# vme_can_fpga_bridge.net
KiCad netlist of a schematic drawn in Altium Designer
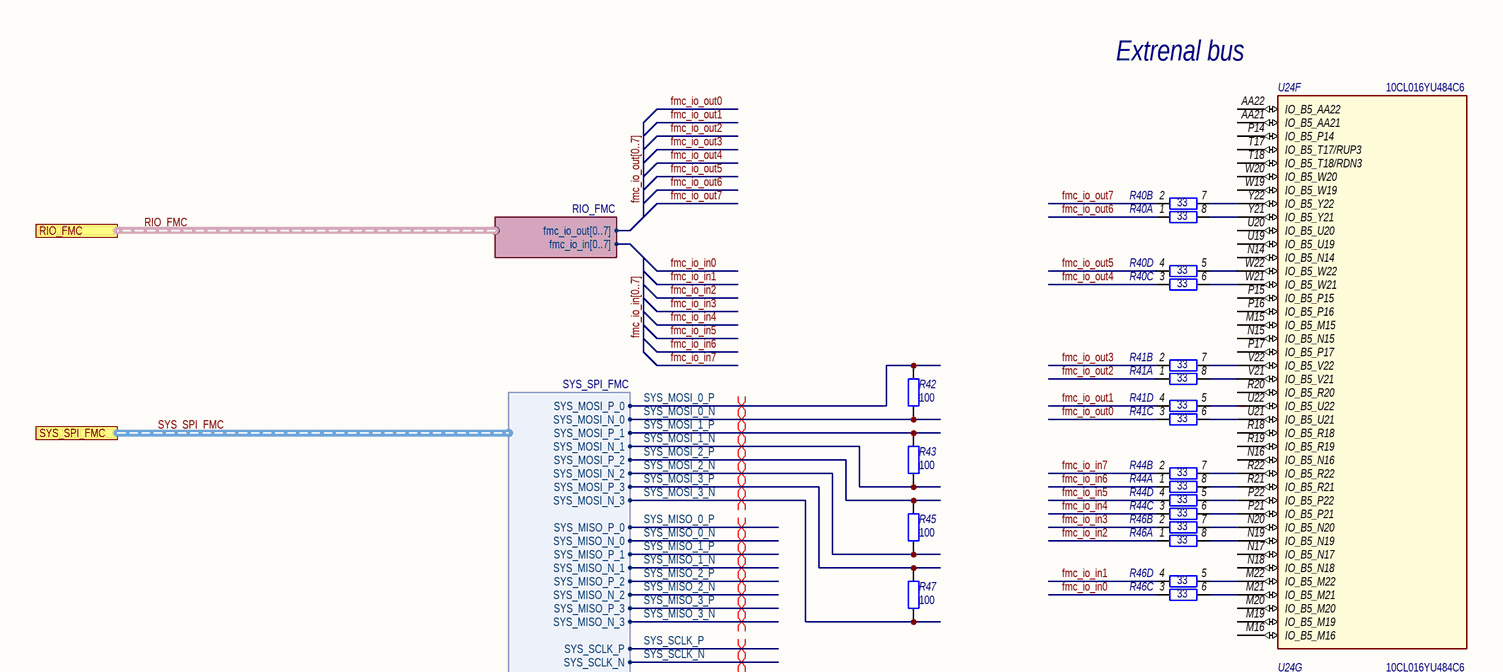
[diagram p0: vme_can_fpga_bridge.SchDoc, top left]
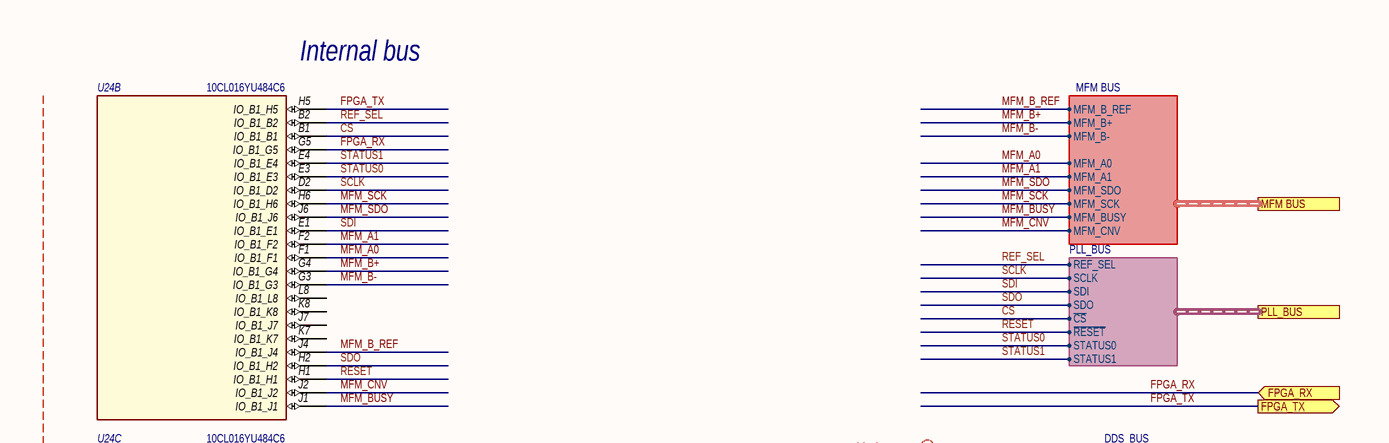
[diagram p1: vme_can_fpga_bridge.SchDoc, top right]
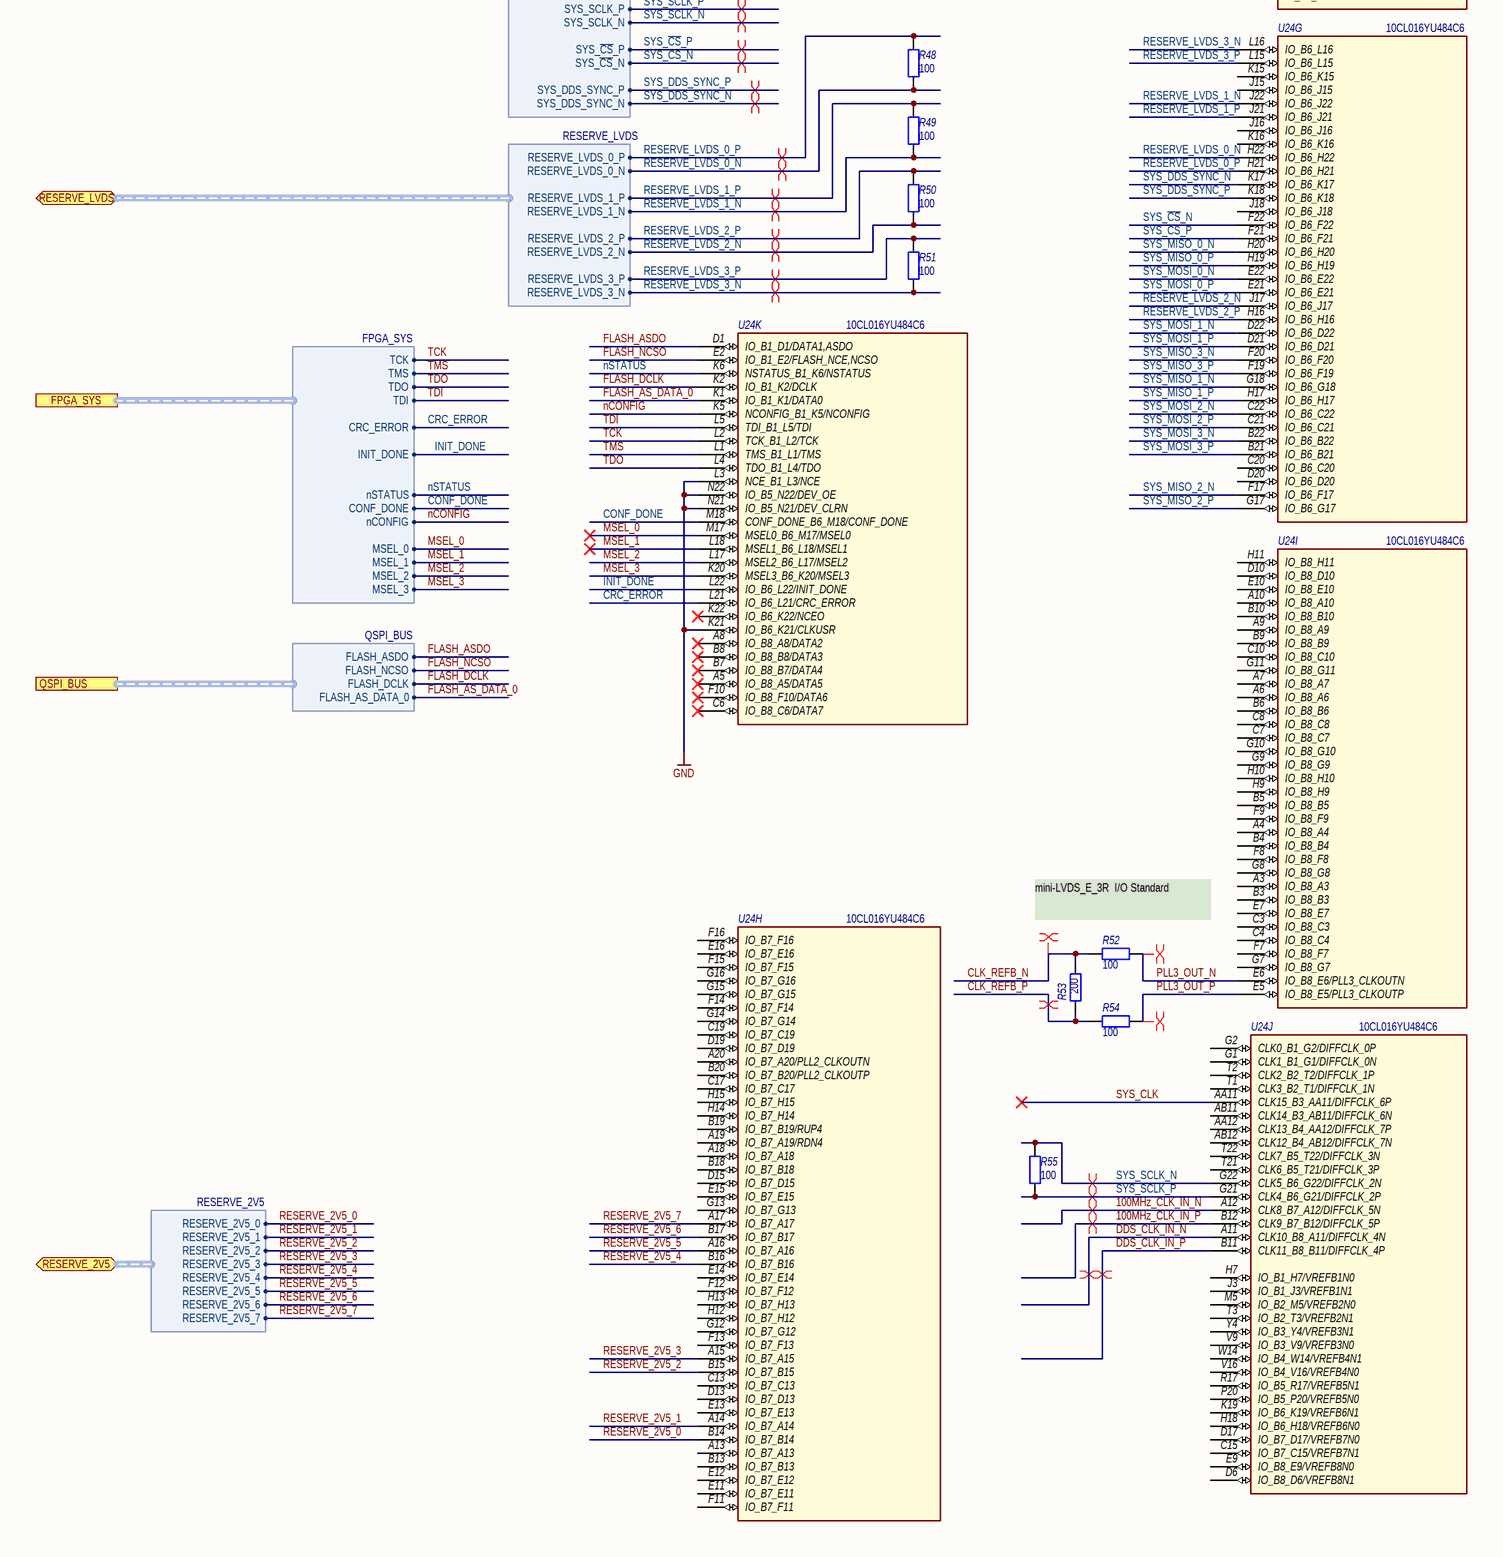
[diagram p2: vme_can_fpga_bridge.SchDoc, bottom left]
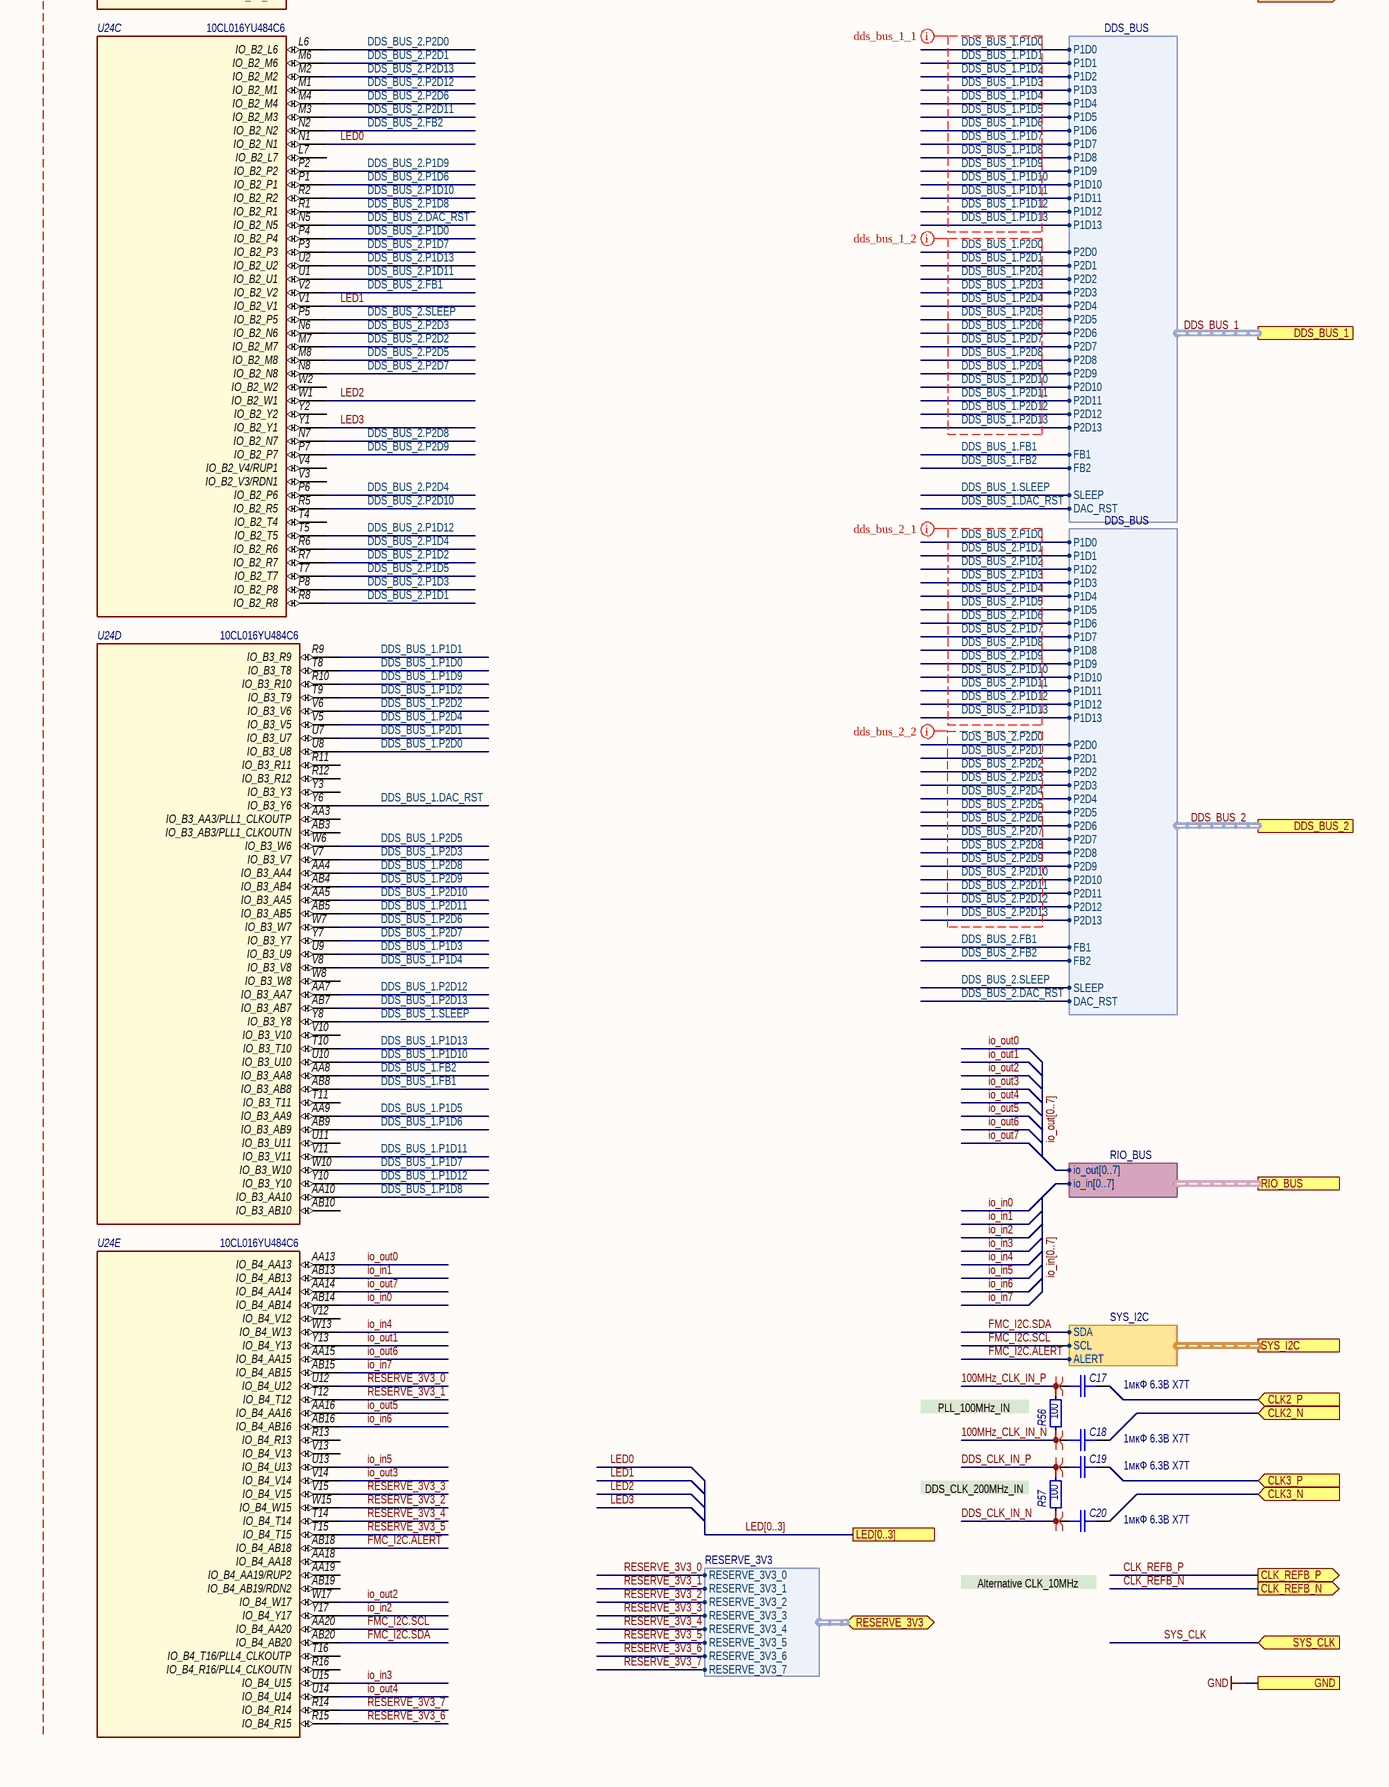
[diagram p3: vme_can_fpga_bridge.SchDoc, bottom right]

(export (version "E")
  (design (tool "Eeschema 10.0.6"))
  (components
    (comp (ref "C17")
      (value "1мкФ 6.3В X7T")
      (footprint "SMD_C0603")
      (description "Capacitor")
      (libsource (lib "Passive") (part "Capacitor"))
    )
    (comp (ref "C18")
      (value "1мкФ 6.3В X7T")
      (footprint "SMD_C0603")
      (description "Capacitor")
      (libsource (lib "Passive") (part "Capacitor"))
    )
    (comp (ref "C19")
      (value "1мкФ 6.3В X7T")
      (footprint "SMD_C0603")
      (description "Capacitor")
      (libsource (lib "Passive") (part "Capacitor"))
    )
    (comp (ref "C20")
      (value "1мкФ 6.3В X7T")
      (footprint "SMD_C0603")
      (description "Capacitor")
      (libsource (lib "Passive") (part "Capacitor"))
    )
    (comp (ref "R40")
      (value "33")
      (footprint "TC124")
      (description "4 Chip Resistor Array")
      (libsource (lib "Passive") (part "Resistor-4"))
    )
    (comp (ref "R41")
      (value "33")
      (footprint "TC124")
      (description "4 Chip Resistor Array")
      (libsource (lib "Passive") (part "Resistor-4"))
    )
    (comp (ref "R42")
      (value "100")
      (footprint "SMD_0603")
      (description "Resistor")
      (libsource (lib "Passive") (part "Resistor"))
    )
    (comp (ref "R43")
      (value "100")
      (footprint "SMD_0603")
      (description "Resistor")
      (libsource (lib "Passive") (part "Resistor"))
    )
    (comp (ref "R44")
      (value "33")
      (footprint "TC124")
      (description "4 Chip Resistor Array")
      (libsource (lib "Passive") (part "Resistor-4"))
    )
    (comp (ref "R45")
      (value "100")
      (footprint "SMD_0603")
      (description "Resistor")
      (libsource (lib "Passive") (part "Resistor"))
    )
    (comp (ref "R46")
      (value "33")
      (footprint "TC124")
      (description "4 Chip Resistor Array")
      (libsource (lib "Passive") (part "Resistor-4"))
    )
    (comp (ref "R47")
      (value "100")
      (footprint "SMD_0603")
      (description "Resistor")
      (libsource (lib "Passive") (part "Resistor"))
    )
    (comp (ref "R48")
      (value "100")
      (footprint "SMD_0603")
      (description "Resistor")
      (libsource (lib "Passive") (part "Resistor"))
    )
    (comp (ref "R49")
      (value "100")
      (footprint "SMD_0603")
      (description "Resistor")
      (libsource (lib "Passive") (part "Resistor"))
    )
    (comp (ref "R50")
      (value "100")
      (footprint "SMD_0603")
      (description "Resistor")
      (libsource (lib "Passive") (part "Resistor"))
    )
    (comp (ref "R51")
      (value "100")
      (footprint "SMD_0603")
      (description "Resistor")
      (libsource (lib "Passive") (part "Resistor"))
    )
    (comp (ref "R52")
      (value "100")
      (footprint "SMD_0603")
      (description "Resistor")
      (libsource (lib "") (part "Resistor_2"))
    )
    (comp (ref "R53")
      (value "200")
      (footprint "SMD_0603")
      (description "Resistor")
      (libsource (lib "") (part "Resistor_1"))
    )
    (comp (ref "R54")
      (value "100")
      (footprint "SMD_0603")
      (description "Resistor")
      (libsource (lib "") (part "Resistor_2"))
    )
    (comp (ref "R55")
      (value "100")
      (footprint "SMD_0603")
      (description "Resistor")
      (libsource (lib "Passive") (part "Resistor"))
    )
    (comp (ref "R56")
      (value "100")
      (footprint "SMD_0603")
      (description "Resistor")
      (libsource (lib "") (part "Resistor_1"))
    )
    (comp (ref "R57")
      (value "100")
      (footprint "SMD_0603")
      (description "Resistor")
      (libsource (lib "") (part "Resistor_1"))
    )
    (comp (ref "U24")
      (value "10CL016YU484")
      (footprint "UBGA-484")
      (description "Intel® Cyclone® 10 LP FPGA")
      (fields (field (name "НАИМЕНОВАНИЕ") "10CL016YU484С6"))
      (libsource (lib "") (part "10CL016_U484_1"))
    )
  )
  (nets
    (net (code "15") (name "/100MHz_CLK_IN_N") (class "Default")
      (node (ref "C18") (pin "1") (pinfunction "1_1") (pintype "passive"))
      (node (ref "R56") (pin "1") (pinfunction "1_1") (pintype "passive"))
      (node (ref "U24") (pin "A12") (pinfunction "CLK8_B7_A12/DIFFCLK_5N_A12") (pintype "bidirectional"))
    )
    (net (code "16") (name "/100MHz_CLK_IN_P") (class "Default")
      (node (ref "C17") (pin "2") (pinfunction "2_2") (pintype "passive"))
      (node (ref "R56") (pin "2") (pinfunction "2_2") (pintype "passive"))
      (node (ref "U24") (pin "B12") (pinfunction "CLK9_B7_B12/DIFFCLK_5P_B12") (pintype "bidirectional"))
    )
    (net (code "17") (name "/CLK2_N") (class "Default")
      (node (ref "C18") (pin "2") (pinfunction "2_2") (pintype "passive"))
    )
    (net (code "18") (name "/CLK2_P") (class "Default")
      (node (ref "C17") (pin "1") (pinfunction "1_1") (pintype "passive"))
    )
    (net (code "19") (name "/CLK3_N") (class "Default")
      (node (ref "C20") (pin "2") (pinfunction "2_2") (pintype "passive"))
    )
    (net (code "20") (name "/CLK3_P") (class "Default")
      (node (ref "C19") (pin "1") (pinfunction "1_1") (pintype "passive"))
    )
    (net (code "21") (name "/CLK_REFB_N") (class "Default")
      (node (ref "R52") (pin "2") (pinfunction "2_2") (pintype "passive"))
      (node (ref "R53") (pin "2") (pinfunction "2_2") (pintype "passive"))
    )
    (net (code "22") (name "/CLK_REFB_P") (class "Default")
      (node (ref "R53") (pin "1") (pinfunction "1_1") (pintype "passive"))
      (node (ref "R54") (pin "2") (pinfunction "2_2") (pintype "passive"))
    )
    (net (code "23") (name "/CONF_DONE") (class "Default")
      (node (ref "U24") (pin "M18") (pinfunction "CONF_DONE_B6_M18/CONF_DONE_M18") (pintype "bidirectional"))
    )
    (net (code "24") (name "/CRC_ERROR") (class "Default")
      (node (ref "U24") (pin "L21") (pinfunction "IO_B6_L21/CRC_ERROR_L21") (pintype "bidirectional"))
    )
    (net (code "25") (name "/DDS_BUS_1.DAC_RST") (class "Default")
      (node (ref "U24") (pin "Y6") (pinfunction "IO_B3_Y6_Y6") (pintype "bidirectional"))
    )
    (net (code "26") (name "/DDS_BUS_1.FB1") (class "Default")
      (node (ref "U24") (pin "AB8") (pinfunction "IO_B3_AB8_AB8") (pintype "bidirectional"))
    )
    (net (code "27") (name "/DDS_BUS_1.FB2") (class "Default")
      (node (ref "U24") (pin "AA8") (pinfunction "IO_B3_AA8_AA8") (pintype "bidirectional"))
    )
    (net (code "28") (name "/DDS_BUS_1.P1D0") (class "Default")
      (node (ref "U24") (pin "T8") (pinfunction "IO_B3_T8_T8") (pintype "bidirectional"))
    )
    (net (code "29") (name "/DDS_BUS_1.P1D1") (class "Default")
      (node (ref "U24") (pin "R9") (pinfunction "IO_B3_R9_R9") (pintype "bidirectional"))
    )
    (net (code "30") (name "/DDS_BUS_1.P1D2") (class "Default")
      (node (ref "U24") (pin "T9") (pinfunction "IO_B3_T9_T9") (pintype "bidirectional"))
    )
    (net (code "31") (name "/DDS_BUS_1.P1D3") (class "Default")
      (node (ref "U24") (pin "U9") (pinfunction "IO_B3_U9_U9") (pintype "bidirectional"))
    )
    (net (code "32") (name "/DDS_BUS_1.P1D4") (class "Default")
      (node (ref "U24") (pin "V8") (pinfunction "IO_B3_V8_V8") (pintype "bidirectional"))
    )
    (net (code "33") (name "/DDS_BUS_1.P1D5") (class "Default")
      (node (ref "U24") (pin "AA9") (pinfunction "IO_B3_AA9_AA9") (pintype "bidirectional"))
    )
    (net (code "34") (name "/DDS_BUS_1.P1D6") (class "Default")
      (node (ref "U24") (pin "AB9") (pinfunction "IO_B3_AB9_AB9") (pintype "bidirectional"))
    )
    (net (code "35") (name "/DDS_BUS_1.P1D7") (class "Default")
      (node (ref "U24") (pin "W10") (pinfunction "IO_B3_W10_W10") (pintype "bidirectional"))
    )
    (net (code "36") (name "/DDS_BUS_1.P1D8") (class "Default")
      (node (ref "U24") (pin "AA10") (pinfunction "IO_B3_AA10_AA10") (pintype "bidirectional"))
    )
    (net (code "37") (name "/DDS_BUS_1.P1D9") (class "Default")
      (node (ref "U24") (pin "R10") (pinfunction "IO_B3_R10_R10") (pintype "bidirectional"))
    )
    (net (code "38") (name "/DDS_BUS_1.P1D10") (class "Default")
      (node (ref "U24") (pin "U10") (pinfunction "IO_B3_U10_U10") (pintype "bidirectional"))
    )
    (net (code "39") (name "/DDS_BUS_1.P1D11") (class "Default")
      (node (ref "U24") (pin "V11") (pinfunction "IO_B3_V11_V11") (pintype "bidirectional"))
    )
    (net (code "40") (name "/DDS_BUS_1.P1D12") (class "Default")
      (node (ref "U24") (pin "Y10") (pinfunction "IO_B3_Y10_Y10") (pintype "bidirectional"))
    )
    (net (code "41") (name "/DDS_BUS_1.P1D13") (class "Default")
      (node (ref "U24") (pin "T10") (pinfunction "IO_B3_T10_T10") (pintype "bidirectional"))
    )
    (net (code "42") (name "/DDS_BUS_1.P2D0") (class "Default")
      (node (ref "U24") (pin "U8") (pinfunction "IO_B3_U8_U8") (pintype "bidirectional"))
    )
    (net (code "43") (name "/DDS_BUS_1.P2D1") (class "Default")
      (node (ref "U24") (pin "U7") (pinfunction "IO_B3_U7_U7") (pintype "bidirectional"))
    )
    (net (code "44") (name "/DDS_BUS_1.P2D2") (class "Default")
      (node (ref "U24") (pin "V6") (pinfunction "IO_B3_V6_V6") (pintype "bidirectional"))
    )
    (net (code "45") (name "/DDS_BUS_1.P2D3") (class "Default")
      (node (ref "U24") (pin "V7") (pinfunction "IO_B3_V7_V7") (pintype "bidirectional"))
    )
    (net (code "46") (name "/DDS_BUS_1.P2D4") (class "Default")
      (node (ref "U24") (pin "V5") (pinfunction "IO_B3_V5_V5") (pintype "bidirectional"))
    )
    (net (code "47") (name "/DDS_BUS_1.P2D5") (class "Default")
      (node (ref "U24") (pin "W6") (pinfunction "IO_B3_W6_W6") (pintype "bidirectional"))
    )
    (net (code "48") (name "/DDS_BUS_1.P2D6") (class "Default")
      (node (ref "U24") (pin "W7") (pinfunction "IO_B3_W7_W7") (pintype "bidirectional"))
    )
    (net (code "49") (name "/DDS_BUS_1.P2D7") (class "Default")
      (node (ref "U24") (pin "Y7") (pinfunction "IO_B3_Y7_Y7") (pintype "bidirectional"))
    )
    (net (code "50") (name "/DDS_BUS_1.P2D8") (class "Default")
      (node (ref "U24") (pin "AA4") (pinfunction "IO_B3_AA4_AA4") (pintype "bidirectional"))
    )
    (net (code "51") (name "/DDS_BUS_1.P2D9") (class "Default")
      (node (ref "U24") (pin "AB4") (pinfunction "IO_B3_AB4_AB4") (pintype "bidirectional"))
    )
    (net (code "52") (name "/DDS_BUS_1.P2D10") (class "Default")
      (node (ref "U24") (pin "AA5") (pinfunction "IO_B3_AA5_AA5") (pintype "bidirectional"))
    )
    (net (code "53") (name "/DDS_BUS_1.P2D11") (class "Default")
      (node (ref "U24") (pin "AB5") (pinfunction "IO_B3_AB5_AB5") (pintype "bidirectional"))
    )
    (net (code "54") (name "/DDS_BUS_1.P2D12") (class "Default")
      (node (ref "U24") (pin "AA7") (pinfunction "IO_B3_AA7_AA7") (pintype "bidirectional"))
    )
    (net (code "55") (name "/DDS_BUS_1.P2D13") (class "Default")
      (node (ref "U24") (pin "AB7") (pinfunction "IO_B3_AB7_AB7") (pintype "bidirectional"))
    )
    (net (code "56") (name "/DDS_BUS_1.SLEEP") (class "Default")
      (node (ref "U24") (pin "Y8") (pinfunction "IO_B3_Y8_Y8") (pintype "bidirectional"))
    )
    (net (code "58") (name "/DDS_BUS_2.DAC_RST") (class "Default")
      (node (ref "U24") (pin "N5") (pinfunction "IO_B2_N5_N5") (pintype "bidirectional"))
    )
    (net (code "59") (name "/DDS_BUS_2.FB1") (class "Default")
      (node (ref "U24") (pin "V2") (pinfunction "IO_B2_V2_V2") (pintype "bidirectional"))
    )
    (net (code "60") (name "/DDS_BUS_2.FB2") (class "Default")
      (node (ref "U24") (pin "N2") (pinfunction "IO_B2_N2_N2") (pintype "bidirectional"))
    )
    (net (code "61") (name "/DDS_BUS_2.P1D0") (class "Default")
      (node (ref "U24") (pin "P4") (pinfunction "IO_B2_P4_P4") (pintype "bidirectional"))
    )
    (net (code "62") (name "/DDS_BUS_2.P1D1") (class "Default")
      (node (ref "U24") (pin "R8") (pinfunction "IO_B2_R8_R8") (pintype "bidirectional"))
    )
    (net (code "63") (name "/DDS_BUS_2.P1D2") (class "Default")
      (node (ref "U24") (pin "R7") (pinfunction "IO_B2_R7_R7") (pintype "bidirectional"))
    )
    (net (code "64") (name "/DDS_BUS_2.P1D3") (class "Default")
      (node (ref "U24") (pin "P8") (pinfunction "IO_B2_P8_P8") (pintype "bidirectional"))
    )
    (net (code "65") (name "/DDS_BUS_2.P1D4") (class "Default")
      (node (ref "U24") (pin "R6") (pinfunction "IO_B2_R6_R6") (pintype "bidirectional"))
    )
    (net (code "66") (name "/DDS_BUS_2.P1D5") (class "Default")
      (node (ref "U24") (pin "T7") (pinfunction "IO_B2_T7_T7") (pintype "bidirectional"))
    )
    (net (code "67") (name "/DDS_BUS_2.P1D6") (class "Default")
      (node (ref "U24") (pin "P1") (pinfunction "IO_B2_P1_P1") (pintype "bidirectional"))
    )
    (net (code "68") (name "/DDS_BUS_2.P1D7") (class "Default")
      (node (ref "U24") (pin "P3") (pinfunction "IO_B2_P3_P3") (pintype "bidirectional"))
    )
    (net (code "69") (name "/DDS_BUS_2.P1D8") (class "Default")
      (node (ref "U24") (pin "R1") (pinfunction "IO_B2_R1_R1") (pintype "bidirectional"))
    )
    (net (code "70") (name "/DDS_BUS_2.P1D9") (class "Default")
      (node (ref "U24") (pin "P2") (pinfunction "IO_B2_P2_P2") (pintype "bidirectional"))
    )
    (net (code "71") (name "/DDS_BUS_2.P1D10") (class "Default")
      (node (ref "U24") (pin "R2") (pinfunction "IO_B2_R2_R2") (pintype "bidirectional"))
    )
    (net (code "72") (name "/DDS_BUS_2.P1D11") (class "Default")
      (node (ref "U24") (pin "U1") (pinfunction "IO_B2_U1_U1") (pintype "bidirectional"))
    )
    (net (code "73") (name "/DDS_BUS_2.P1D12") (class "Default")
      (node (ref "U24") (pin "T5") (pinfunction "IO_B2_T5_T5") (pintype "bidirectional"))
    )
    (net (code "74") (name "/DDS_BUS_2.P1D13") (class "Default")
      (node (ref "U24") (pin "U2") (pinfunction "IO_B2_U2_U2") (pintype "bidirectional"))
    )
    (net (code "75") (name "/DDS_BUS_2.P2D0") (class "Default")
      (node (ref "U24") (pin "L6") (pinfunction "IO_B2_L6_L6") (pintype "bidirectional"))
    )
    (net (code "76") (name "/DDS_BUS_2.P2D1") (class "Default")
      (node (ref "U24") (pin "M6") (pinfunction "IO_B2_M6_M6") (pintype "bidirectional"))
    )
    (net (code "77") (name "/DDS_BUS_2.P2D2") (class "Default")
      (node (ref "U24") (pin "M7") (pinfunction "IO_B2_M7_M7") (pintype "bidirectional"))
    )
    (net (code "78") (name "/DDS_BUS_2.P2D3") (class "Default")
      (node (ref "U24") (pin "N6") (pinfunction "IO_B2_N6_N6") (pintype "bidirectional"))
    )
    (net (code "79") (name "/DDS_BUS_2.P2D4") (class "Default")
      (node (ref "U24") (pin "P6") (pinfunction "IO_B2_P6_P6") (pintype "bidirectional"))
    )
    (net (code "80") (name "/DDS_BUS_2.P2D5") (class "Default")
      (node (ref "U24") (pin "M8") (pinfunction "IO_B2_M8_M8") (pintype "bidirectional"))
    )
    (net (code "81") (name "/DDS_BUS_2.P2D6") (class "Default")
      (node (ref "U24") (pin "M4") (pinfunction "IO_B2_M4_M4") (pintype "bidirectional"))
    )
    (net (code "82") (name "/DDS_BUS_2.P2D7") (class "Default")
      (node (ref "U24") (pin "N8") (pinfunction "IO_B2_N8_N8") (pintype "bidirectional"))
    )
    (net (code "83") (name "/DDS_BUS_2.P2D8") (class "Default")
      (node (ref "U24") (pin "N7") (pinfunction "IO_B2_N7_N7") (pintype "bidirectional"))
    )
    (net (code "84") (name "/DDS_BUS_2.P2D9") (class "Default")
      (node (ref "U24") (pin "P7") (pinfunction "IO_B2_P7_P7") (pintype "bidirectional"))
    )
    (net (code "85") (name "/DDS_BUS_2.P2D10") (class "Default")
      (node (ref "U24") (pin "R5") (pinfunction "IO_B2_R5_R5") (pintype "bidirectional"))
    )
    (net (code "86") (name "/DDS_BUS_2.P2D11") (class "Default")
      (node (ref "U24") (pin "M3") (pinfunction "IO_B2_M3_M3") (pintype "bidirectional"))
    )
    (net (code "87") (name "/DDS_BUS_2.P2D12") (class "Default")
      (node (ref "U24") (pin "M1") (pinfunction "IO_B2_M1_M1") (pintype "bidirectional"))
    )
    (net (code "88") (name "/DDS_BUS_2.P2D13") (class "Default")
      (node (ref "U24") (pin "M2") (pinfunction "IO_B2_M2_M2") (pintype "bidirectional"))
    )
    (net (code "89") (name "/DDS_BUS_2.SLEEP") (class "Default")
      (node (ref "U24") (pin "P5") (pinfunction "IO_B2_P5_P5") (pintype "bidirectional"))
    )
    (net (code "91") (name "/DDS_CLK_IN_N") (class "Default")
      (node (ref "C20") (pin "1") (pinfunction "1_1") (pintype "passive"))
      (node (ref "R57") (pin "1") (pinfunction "1_1") (pintype "passive"))
      (node (ref "U24") (pin "A11") (pinfunction "CLK10_B8_A11/DIFFCLK_4N_A11") (pintype "bidirectional"))
    )
    (net (code "92") (name "/DDS_CLK_IN_P") (class "Default")
      (node (ref "C19") (pin "2") (pinfunction "2_2") (pintype "passive"))
      (node (ref "R57") (pin "2") (pinfunction "2_2") (pintype "passive"))
      (node (ref "U24") (pin "B11") (pinfunction "CLK11_B8_B11/DIFFCLK_4P_B11") (pintype "bidirectional"))
    )
    (net (code "93") (name "/FLASH_ASDO") (class "Default")
      (node (ref "U24") (pin "D1") (pinfunction "IO_B1_D1/DATA1,ASDO_D1") (pintype "bidirectional"))
    )
    (net (code "94") (name "/FLASH_AS_DATA_0") (class "Default")
      (node (ref "U24") (pin "K1") (pinfunction "IO_B1_K1/DATA0_K1") (pintype "bidirectional"))
    )
    (net (code "95") (name "/FLASH_DCLK") (class "Default")
      (node (ref "U24") (pin "K2") (pinfunction "IO_B1_K2/DCLK_K2") (pintype "bidirectional"))
    )
    (net (code "96") (name "/FLASH_NCSO") (class "Default")
      (node (ref "U24") (pin "E2") (pinfunction "IO_B1_E2/FLASH_NCE,NCSO_E2") (pintype "bidirectional"))
    )
    (net (code "97") (name "/FMC_I2C.ALERT") (class "Default")
      (node (ref "U24") (pin "AB18") (pinfunction "IO_B4_AB18_AB18") (pintype "bidirectional"))
    )
    (net (code "98") (name "/FMC_I2C.SCL") (class "Default")
      (node (ref "U24") (pin "AA20") (pinfunction "IO_B4_AA20_AA20") (pintype "bidirectional"))
    )
    (net (code "99") (name "/FMC_I2C.SDA") (class "Default")
      (node (ref "U24") (pin "AB20") (pinfunction "IO_B4_AB20_AB20") (pintype "bidirectional"))
    )
    (net (code "100") (name "/FPGA_RX") (class "Default")
      (node (ref "U24") (pin "G5") (pinfunction "IO_B1_G5_G5") (pintype "bidirectional"))
    )
    (net (code "101") (name "/FPGA_TX") (class "Default")
      (node (ref "U24") (pin "H5") (pinfunction "IO_B1_H5_H5") (pintype "bidirectional"))
    )
    (net (code "102") (name "/INIT_DONE") (class "Default")
      (node (ref "U24") (pin "L22") (pinfunction "IO_B6_L22/INIT_DONE_L22") (pintype "bidirectional"))
    )
    (net (code "103") (name "/LED0") (class "Default")
      (node (ref "U24") (pin "N1") (pinfunction "IO_B2_N1_N1") (pintype "bidirectional"))
    )
    (net (code "104") (name "/LED1") (class "Default")
      (node (ref "U24") (pin "V1") (pinfunction "IO_B2_V1_V1") (pintype "bidirectional"))
    )
    (net (code "105") (name "/LED2") (class "Default")
      (node (ref "U24") (pin "W1") (pinfunction "IO_B2_W1_W1") (pintype "bidirectional"))
    )
    (net (code "106") (name "/LED3") (class "Default")
      (node (ref "U24") (pin "Y1") (pinfunction "IO_B2_Y1_Y1") (pintype "bidirectional"))
    )
    (net (code "108") (name "/MFM_A0") (class "Default")
      (node (ref "U24") (pin "F1") (pinfunction "IO_B1_F1_F1") (pintype "bidirectional"))
    )
    (net (code "109") (name "/MFM_A1") (class "Default")
      (node (ref "U24") (pin "F2") (pinfunction "IO_B1_F2_F2") (pintype "bidirectional"))
    )
    (net (code "110") (name "/MFM_B+") (class "Default")
      (node (ref "U24") (pin "G4") (pinfunction "IO_B1_G4_G4") (pintype "bidirectional"))
    )
    (net (code "111") (name "/MFM_B-") (class "Default")
      (node (ref "U24") (pin "G3") (pinfunction "IO_B1_G3_G3") (pintype "bidirectional"))
    )
    (net (code "112") (name "/MFM_BUSY") (class "Default")
      (node (ref "U24") (pin "J1") (pinfunction "IO_B1_J1_J1") (pintype "bidirectional"))
    )
    (net (code "113") (name "/MFM_B_REF") (class "Default")
      (node (ref "U24") (pin "J4") (pinfunction "IO_B1_J4_J4") (pintype "bidirectional"))
    )
    (net (code "114") (name "/MFM_CNV") (class "Default")
      (node (ref "U24") (pin "J2") (pinfunction "IO_B1_J2_J2") (pintype "bidirectional"))
    )
    (net (code "115") (name "/MFM_SCK") (class "Default")
      (node (ref "U24") (pin "H6") (pinfunction "IO_B1_H6_H6") (pintype "bidirectional"))
    )
    (net (code "116") (name "/MFM_SDO") (class "Default")
      (node (ref "U24") (pin "J6") (pinfunction "IO_B1_J6_J6") (pintype "bidirectional"))
    )
    (net (code "117") (name "/MSEL_0") (class "Default")
      (node (ref "U24") (pin "M17") (pinfunction "MSEL0_B6_M17/MSEL0_M17") (pintype "bidirectional+no_connect"))
    )
    (net (code "118") (name "/MSEL_1") (class "Default")
      (node (ref "U24") (pin "L18") (pinfunction "MSEL1_B6_L18/MSEL1_L18") (pintype "bidirectional+no_connect"))
    )
    (net (code "119") (name "/MSEL_2") (class "Default")
      (node (ref "U24") (pin "L17") (pinfunction "MSEL2_B6_L17/MSEL2_L17") (pintype "bidirectional"))
    )
    (net (code "120") (name "/MSEL_3") (class "Default")
      (node (ref "U24") (pin "K20") (pinfunction "MSEL3_B6_K20/MSEL3_K20") (pintype "bidirectional"))
    )
    (net (code "121") (name "/PLL3_OUT_N") (class "Default")
      (node (ref "R52") (pin "1") (pinfunction "1_1") (pintype "passive"))
      (node (ref "U24") (pin "E6") (pinfunction "IO_B8_E6/PLL3_CLKOUTN_E6") (pintype "bidirectional"))
    )
    (net (code "122") (name "/PLL3_OUT_P") (class "Default")
      (node (ref "R54") (pin "1") (pinfunction "1_1") (pintype "passive"))
      (node (ref "U24") (pin "E5") (pinfunction "IO_B8_E5/PLL3_CLKOUTP_E5") (pintype "bidirectional"))
    )
    (net (code "123") (name "/REF_SEL") (class "Default")
      (node (ref "U24") (pin "B2") (pinfunction "IO_B1_B2_B2") (pintype "bidirectional"))
    )
    (net (code "124") (name "/RESERVE_2V5_0") (class "Default")
      (node (ref "U24") (pin "B14") (pinfunction "IO_B7_B14_B14") (pintype "bidirectional"))
    )
    (net (code "125") (name "/RESERVE_2V5_1") (class "Default")
      (node (ref "U24") (pin "A14") (pinfunction "IO_B7_A14_A14") (pintype "bidirectional"))
    )
    (net (code "126") (name "/RESERVE_2V5_2") (class "Default")
      (node (ref "U24") (pin "B15") (pinfunction "IO_B7_B15_B15") (pintype "bidirectional"))
    )
    (net (code "127") (name "/RESERVE_2V5_3") (class "Default")
      (node (ref "U24") (pin "A15") (pinfunction "IO_B7_A15_A15") (pintype "bidirectional"))
    )
    (net (code "128") (name "/RESERVE_2V5_4") (class "Default")
      (node (ref "U24") (pin "B16") (pinfunction "IO_B7_B16_B16") (pintype "bidirectional"))
    )
    (net (code "129") (name "/RESERVE_2V5_5") (class "Default")
      (node (ref "U24") (pin "A16") (pinfunction "IO_B7_A16_A16") (pintype "bidirectional"))
    )
    (net (code "130") (name "/RESERVE_2V5_6") (class "Default")
      (node (ref "U24") (pin "B17") (pinfunction "IO_B7_B17_B17") (pintype "bidirectional"))
    )
    (net (code "131") (name "/RESERVE_2V5_7") (class "Default")
      (node (ref "U24") (pin "A17") (pinfunction "IO_B7_A17_A17") (pintype "bidirectional"))
    )
    (net (code "132") (name "/RESERVE_3V3_0") (class "Default")
      (node (ref "U24") (pin "U12") (pinfunction "IO_B4_U12_U12") (pintype "bidirectional"))
    )
    (net (code "133") (name "/RESERVE_3V3_1") (class "Default")
      (node (ref "U24") (pin "T12") (pinfunction "IO_B4_T12_T12") (pintype "bidirectional"))
    )
    (net (code "134") (name "/RESERVE_3V3_2") (class "Default")
      (node (ref "U24") (pin "W15") (pinfunction "IO_B4_W15_W15") (pintype "bidirectional"))
    )
    (net (code "135") (name "/RESERVE_3V3_3") (class "Default")
      (node (ref "U24") (pin "V15") (pinfunction "IO_B4_V15_V15") (pintype "bidirectional"))
    )
    (net (code "136") (name "/RESERVE_3V3_4") (class "Default")
      (node (ref "U24") (pin "T14") (pinfunction "IO_B4_T14_T14") (pintype "bidirectional"))
    )
    (net (code "137") (name "/RESERVE_3V3_5") (class "Default")
      (node (ref "U24") (pin "T15") (pinfunction "IO_B4_T15_T15") (pintype "bidirectional"))
    )
    (net (code "138") (name "/RESERVE_3V3_6") (class "Default")
      (node (ref "U24") (pin "R15") (pinfunction "IO_B4_R15_R15") (pintype "bidirectional"))
    )
    (net (code "139") (name "/RESERVE_3V3_7") (class "Default")
      (node (ref "U24") (pin "R14") (pinfunction "IO_B4_R14_R14") (pintype "bidirectional"))
    )
    (net (code "140") (name "/RESERVE_LVDS_0_N") (class "Default")
      (node (ref "R48") (pin "2") (pinfunction "2_2") (pintype "passive"))
      (node (ref "U24") (pin "H22") (pinfunction "IO_B6_H22_H22") (pintype "bidirectional"))
    )
    (net (code "141") (name "/RESERVE_LVDS_0_P") (class "Default")
      (node (ref "R48") (pin "1") (pinfunction "1_1") (pintype "passive"))
      (node (ref "U24") (pin "H21") (pinfunction "IO_B6_H21_H21") (pintype "bidirectional"))
    )
    (net (code "142") (name "/RESERVE_LVDS_1_N") (class "Default")
      (node (ref "R49") (pin "2") (pinfunction "2_2") (pintype "passive"))
      (node (ref "U24") (pin "J22") (pinfunction "IO_B6_J22_J22") (pintype "bidirectional"))
    )
    (net (code "143") (name "/RESERVE_LVDS_1_P") (class "Default")
      (node (ref "R49") (pin "1") (pinfunction "1_1") (pintype "passive"))
      (node (ref "U24") (pin "J21") (pinfunction "IO_B6_J21_J21") (pintype "bidirectional"))
    )
    (net (code "144") (name "/RESERVE_LVDS_2_N") (class "Default")
      (node (ref "R50") (pin "2") (pinfunction "2_2") (pintype "passive"))
      (node (ref "U24") (pin "J17") (pinfunction "IO_B6_J17_J17") (pintype "bidirectional"))
    )
    (net (code "145") (name "/RESERVE_LVDS_2_P") (class "Default")
      (node (ref "R50") (pin "1") (pinfunction "1_1") (pintype "passive"))
      (node (ref "U24") (pin "H16") (pinfunction "IO_B6_H16_H16") (pintype "bidirectional"))
    )
    (net (code "146") (name "/RESERVE_LVDS_3_N") (class "Default")
      (node (ref "R51") (pin "2") (pinfunction "2_2") (pintype "passive"))
      (node (ref "U24") (pin "L16") (pinfunction "IO_B6_L16_L16") (pintype "bidirectional"))
    )
    (net (code "147") (name "/RESERVE_LVDS_3_P") (class "Default")
      (node (ref "R51") (pin "1") (pinfunction "1_1") (pintype "passive"))
      (node (ref "U24") (pin "L15") (pinfunction "IO_B6_L15_L15") (pintype "bidirectional"))
    )
    (net (code "148") (name "/SCLK") (class "Default")
      (node (ref "U24") (pin "D2") (pinfunction "IO_B1_D2_D2") (pintype "bidirectional"))
    )
    (net (code "149") (name "/SDI") (class "Default")
      (node (ref "U24") (pin "E1") (pinfunction "IO_B1_E1_E1") (pintype "bidirectional"))
    )
    (net (code "150") (name "/SDO") (class "Default")
      (node (ref "U24") (pin "H2") (pinfunction "IO_B1_H2_H2") (pintype "bidirectional"))
    )
    (net (code "151") (name "/STATUS0") (class "Default")
      (node (ref "U24") (pin "E3") (pinfunction "IO_B1_E3_E3") (pintype "bidirectional"))
    )
    (net (code "152") (name "/STATUS1") (class "Default")
      (node (ref "U24") (pin "E4") (pinfunction "IO_B1_E4_E4") (pintype "bidirectional"))
    )
    (net (code "153") (name "/SYS_CLK") (class "Default")
      (node (ref "U24") (pin "AA11") (pinfunction "CLK15_B3_AA11/DIFFCLK_6P_AA11") (pintype "bidirectional+no_connect"))
    )
    (net (code "154") (name "/SYS_DDS_SYNC_N") (class "Default")
      (node (ref "U24") (pin "K17") (pinfunction "IO_B6_K17_K17") (pintype "bidirectional"))
    )
    (net (code "155") (name "/SYS_DDS_SYNC_P") (class "Default")
      (node (ref "U24") (pin "K18") (pinfunction "IO_B6_K18_K18") (pintype "bidirectional"))
    )
    (net (code "156") (name "/SYS_MISO_0_N") (class "Default")
      (node (ref "U24") (pin "H20") (pinfunction "IO_B6_H20_H20") (pintype "bidirectional"))
    )
    (net (code "157") (name "/SYS_MISO_0_P") (class "Default")
      (node (ref "U24") (pin "H19") (pinfunction "IO_B6_H19_H19") (pintype "bidirectional"))
    )
    (net (code "158") (name "/SYS_MISO_1_N") (class "Default")
      (node (ref "U24") (pin "G18") (pinfunction "IO_B6_G18_G18") (pintype "bidirectional"))
    )
    (net (code "159") (name "/SYS_MISO_1_P") (class "Default")
      (node (ref "U24") (pin "H17") (pinfunction "IO_B6_H17_H17") (pintype "bidirectional"))
    )
    (net (code "160") (name "/SYS_MISO_2_N") (class "Default")
      (node (ref "U24") (pin "F17") (pinfunction "IO_B6_F17_F17") (pintype "bidirectional"))
    )
    (net (code "161") (name "/SYS_MISO_2_P") (class "Default")
      (node (ref "U24") (pin "G17") (pinfunction "IO_B6_G17_G17") (pintype "bidirectional"))
    )
    (net (code "162") (name "/SYS_MISO_3_N") (class "Default")
      (node (ref "U24") (pin "F20") (pinfunction "IO_B6_F20_F20") (pintype "bidirectional"))
    )
    (net (code "163") (name "/SYS_MISO_3_P") (class "Default")
      (node (ref "U24") (pin "F19") (pinfunction "IO_B6_F19_F19") (pintype "bidirectional"))
    )
    (net (code "164") (name "/SYS_MOSI_0_N") (class "Default")
      (node (ref "R42") (pin "2") (pinfunction "2_2") (pintype "passive"))
      (node (ref "U24") (pin "E22") (pinfunction "IO_B6_E22_E22") (pintype "bidirectional"))
    )
    (net (code "165") (name "/SYS_MOSI_0_P") (class "Default")
      (node (ref "R42") (pin "1") (pinfunction "1_1") (pintype "passive"))
      (node (ref "U24") (pin "E21") (pinfunction "IO_B6_E21_E21") (pintype "bidirectional"))
    )
    (net (code "166") (name "/SYS_MOSI_1_N") (class "Default")
      (node (ref "R43") (pin "2") (pinfunction "2_2") (pintype "passive"))
      (node (ref "U24") (pin "D22") (pinfunction "IO_B6_D22_D22") (pintype "bidirectional"))
    )
    (net (code "167") (name "/SYS_MOSI_1_P") (class "Default")
      (node (ref "R43") (pin "1") (pinfunction "1_1") (pintype "passive"))
      (node (ref "U24") (pin "D21") (pinfunction "IO_B6_D21_D21") (pintype "bidirectional"))
    )
    (net (code "168") (name "/SYS_MOSI_2_N") (class "Default")
      (node (ref "R45") (pin "2") (pinfunction "2_2") (pintype "passive"))
      (node (ref "U24") (pin "C22") (pinfunction "IO_B6_C22_C22") (pintype "bidirectional"))
    )
    (net (code "169") (name "/SYS_MOSI_2_P") (class "Default")
      (node (ref "R45") (pin "1") (pinfunction "1_1") (pintype "passive"))
      (node (ref "U24") (pin "C21") (pinfunction "IO_B6_C21_C21") (pintype "bidirectional"))
    )
    (net (code "170") (name "/SYS_MOSI_3_N") (class "Default")
      (node (ref "R47") (pin "2") (pinfunction "2_2") (pintype "passive"))
      (node (ref "U24") (pin "B22") (pinfunction "IO_B6_B22_B22") (pintype "bidirectional"))
    )
    (net (code "171") (name "/SYS_MOSI_3_P") (class "Default")
      (node (ref "R47") (pin "1") (pinfunction "1_1") (pintype "passive"))
      (node (ref "U24") (pin "B21") (pinfunction "IO_B6_B21_B21") (pintype "bidirectional"))
    )
    (net (code "172") (name "/SYS_SCLK_N") (class "Default")
      (node (ref "R55") (pin "1") (pinfunction "1_1") (pintype "passive"))
      (node (ref "U24") (pin "G22") (pinfunction "CLK5_B6_G22/DIFFCLK_2N_G22") (pintype "bidirectional"))
    )
    (net (code "173") (name "/SYS_SCLK_P") (class "Default")
      (node (ref "R55") (pin "2") (pinfunction "2_2") (pintype "passive"))
      (node (ref "U24") (pin "G21") (pinfunction "CLK4_B6_G21/DIFFCLK_2P_G21") (pintype "bidirectional"))
    )
    (net (code "175") (name "/SYS_~{CS}_N") (class "Default")
      (node (ref "U24") (pin "F22") (pinfunction "IO_B6_F22_F22") (pintype "bidirectional"))
    )
    (net (code "176") (name "/SYS_~{CS}_P") (class "Default")
      (node (ref "U24") (pin "F21") (pinfunction "IO_B6_F21_F21") (pintype "bidirectional"))
    )
    (net (code "177") (name "/TCK") (class "Default")
      (node (ref "U24") (pin "L2") (pinfunction "TCK_B1_L2/TCK_L2") (pintype "bidirectional"))
    )
    (net (code "178") (name "/TDI") (class "Default")
      (node (ref "U24") (pin "L5") (pinfunction "TDI_B1_L5/TDI_L5") (pintype "bidirectional"))
    )
    (net (code "179") (name "/TDO") (class "Default")
      (node (ref "U24") (pin "L4") (pinfunction "TDO_B1_L4/TDO_L4") (pintype "bidirectional"))
    )
    (net (code "180") (name "/TMS") (class "Default")
      (node (ref "U24") (pin "L1") (pinfunction "TMS_B1_L1/TMS_L1") (pintype "bidirectional"))
    )
    (net (code "181") (name "/fmc_io_in0") (class "Default")
      (node (ref "R46") (pin "3") (pinfunction "3_3") (pintype "passive"))
    )
    (net (code "182") (name "/fmc_io_in1") (class "Default")
      (node (ref "R46") (pin "4") (pinfunction "4_4") (pintype "passive"))
    )
    (net (code "183") (name "/fmc_io_in2") (class "Default")
      (node (ref "R46") (pin "1") (pinfunction "1_1") (pintype "passive"))
    )
    (net (code "184") (name "/fmc_io_in3") (class "Default")
      (node (ref "R46") (pin "2") (pinfunction "2_2") (pintype "passive"))
    )
    (net (code "185") (name "/fmc_io_in4") (class "Default")
      (node (ref "R44") (pin "3") (pinfunction "3_3") (pintype "passive"))
    )
    (net (code "186") (name "/fmc_io_in5") (class "Default")
      (node (ref "R44") (pin "4") (pinfunction "4_4") (pintype "passive"))
    )
    (net (code "187") (name "/fmc_io_in6") (class "Default")
      (node (ref "R44") (pin "1") (pinfunction "1_1") (pintype "passive"))
    )
    (net (code "188") (name "/fmc_io_in7") (class "Default")
      (node (ref "R44") (pin "2") (pinfunction "2_2") (pintype "passive"))
    )
    (net (code "189") (name "/fmc_io_out0") (class "Default")
      (node (ref "R41") (pin "3") (pinfunction "3_3") (pintype "passive"))
    )
    (net (code "190") (name "/fmc_io_out1") (class "Default")
      (node (ref "R41") (pin "4") (pinfunction "4_4") (pintype "passive"))
    )
    (net (code "191") (name "/fmc_io_out2") (class "Default")
      (node (ref "R41") (pin "1") (pinfunction "1_1") (pintype "passive"))
    )
    (net (code "192") (name "/fmc_io_out3") (class "Default")
      (node (ref "R41") (pin "2") (pinfunction "2_2") (pintype "passive"))
    )
    (net (code "193") (name "/fmc_io_out4") (class "Default")
      (node (ref "R40") (pin "3") (pinfunction "3_3") (pintype "passive"))
    )
    (net (code "194") (name "/fmc_io_out5") (class "Default")
      (node (ref "R40") (pin "4") (pinfunction "4_4") (pintype "passive"))
    )
    (net (code "195") (name "/fmc_io_out6") (class "Default")
      (node (ref "R40") (pin "1") (pinfunction "1_1") (pintype "passive"))
    )
    (net (code "196") (name "/fmc_io_out7") (class "Default")
      (node (ref "R40") (pin "2") (pinfunction "2_2") (pintype "passive"))
    )
    (net (code "198") (name "/io_in0") (class "Default")
      (node (ref "U24") (pin "AB14") (pinfunction "IO_B4_AB14_AB14") (pintype "bidirectional"))
    )
    (net (code "199") (name "/io_in1") (class "Default")
      (node (ref "U24") (pin "AB13") (pinfunction "IO_B4_AB13_AB13") (pintype "bidirectional"))
    )
    (net (code "200") (name "/io_in2") (class "Default")
      (node (ref "U24") (pin "Y17") (pinfunction "IO_B4_Y17_Y17") (pintype "bidirectional"))
    )
    (net (code "201") (name "/io_in3") (class "Default")
      (node (ref "U24") (pin "U15") (pinfunction "IO_B4_U15_U15") (pintype "bidirectional"))
    )
    (net (code "202") (name "/io_in4") (class "Default")
      (node (ref "U24") (pin "W13") (pinfunction "IO_B4_W13_W13") (pintype "bidirectional"))
    )
    (net (code "203") (name "/io_in5") (class "Default")
      (node (ref "U24") (pin "U13") (pinfunction "IO_B4_U13_U13") (pintype "bidirectional"))
    )
    (net (code "204") (name "/io_in6") (class "Default")
      (node (ref "U24") (pin "AB16") (pinfunction "IO_B4_AB16_AB16") (pintype "bidirectional"))
    )
    (net (code "205") (name "/io_in7") (class "Default")
      (node (ref "U24") (pin "AB15") (pinfunction "IO_B4_AB15_AB15") (pintype "bidirectional"))
    )
    (net (code "207") (name "/io_out0") (class "Default")
      (node (ref "U24") (pin "AA13") (pinfunction "IO_B4_AA13_AA13") (pintype "bidirectional"))
    )
    (net (code "208") (name "/io_out1") (class "Default")
      (node (ref "U24") (pin "Y13") (pinfunction "IO_B4_Y13_Y13") (pintype "bidirectional"))
    )
    (net (code "209") (name "/io_out2") (class "Default")
      (node (ref "U24") (pin "W17") (pinfunction "IO_B4_W17_W17") (pintype "bidirectional"))
    )
    (net (code "210") (name "/io_out3") (class "Default")
      (node (ref "U24") (pin "V14") (pinfunction "IO_B4_V14_V14") (pintype "bidirectional"))
    )
    (net (code "211") (name "/io_out4") (class "Default")
      (node (ref "U24") (pin "U14") (pinfunction "IO_B4_U14_U14") (pintype "bidirectional"))
    )
    (net (code "212") (name "/io_out5") (class "Default")
      (node (ref "U24") (pin "AA16") (pinfunction "IO_B4_AA16_AA16") (pintype "bidirectional"))
    )
    (net (code "213") (name "/io_out6") (class "Default")
      (node (ref "U24") (pin "AA15") (pinfunction "IO_B4_AA15_AA15") (pintype "bidirectional"))
    )
    (net (code "214") (name "/io_out7") (class "Default")
      (node (ref "U24") (pin "AA14") (pinfunction "IO_B4_AA14_AA14") (pintype "bidirectional"))
    )
    (net (code "216") (name "/nCONFIG") (class "Default")
      (node (ref "U24") (pin "K5") (pinfunction "NCONFIG_B1_K5/NCONFIG_K5") (pintype "bidirectional"))
    )
    (net (code "217") (name "/nSTATUS") (class "Default")
      (node (ref "U24") (pin "K6") (pinfunction "NSTATUS_B1_K6/NSTATUS_K6") (pintype "bidirectional"))
    )
    (net (code "228") (name "/~{CS}") (class "Default")
      (node (ref "U24") (pin "B1") (pinfunction "IO_B1_B1_B1") (pintype "bidirectional"))
    )
    (net (code "229") (name "/~{RESET}") (class "Default")
      (node (ref "U24") (pin "H1") (pinfunction "IO_B1_H1_H1") (pintype "bidirectional"))
    )
    (net (code "230") (name "GND") (class "Default")
      (node (ref "U24") (pin "K21") (pinfunction "IO_B6_K21/CLKUSR_K21") (pintype "bidirectional"))
      (node (ref "U24") (pin "L3") (pinfunction "NCE_B1_L3/NCE_L3") (pintype "bidirectional"))
      (node (ref "U24") (pin "N21") (pinfunction "IO_B5_N21/DEV_CLRN_N21") (pintype "bidirectional"))
      (node (ref "U24") (pin "N22") (pinfunction "IO_B5_N22/DEV_OE_N22") (pintype "bidirectional"))
    )
    (net (code "231") (name "Net-(U24F-IO_B5_M21)") (class "Default")
      (node (ref "R46") (pin "6") (pinfunction "6_6") (pintype "passive"))
      (node (ref "U24") (pin "M21") (pinfunction "IO_B5_M21_M21") (pintype "bidirectional"))
    )
    (net (code "232") (name "Net-(U24F-IO_B5_M22)") (class "Default")
      (node (ref "R46") (pin "5") (pinfunction "5_5") (pintype "passive"))
      (node (ref "U24") (pin "M22") (pinfunction "IO_B5_M22_M22") (pintype "bidirectional"))
    )
    (net (code "233") (name "Net-(U24F-IO_B5_N19)") (class "Default")
      (node (ref "R46") (pin "8") (pinfunction "8_8") (pintype "passive"))
      (node (ref "U24") (pin "N19") (pinfunction "IO_B5_N19_N19") (pintype "bidirectional"))
    )
    (net (code "234") (name "Net-(U24F-IO_B5_N20)") (class "Default")
      (node (ref "R46") (pin "7") (pinfunction "7_7") (pintype "passive"))
      (node (ref "U24") (pin "N20") (pinfunction "IO_B5_N20_N20") (pintype "bidirectional"))
    )
    (net (code "235") (name "Net-(U24F-IO_B5_P21)") (class "Default")
      (node (ref "R44") (pin "6") (pinfunction "6_6") (pintype "passive"))
      (node (ref "U24") (pin "P21") (pinfunction "IO_B5_P21_P21") (pintype "bidirectional"))
    )
    (net (code "236") (name "Net-(U24F-IO_B5_P22)") (class "Default")
      (node (ref "R44") (pin "5") (pinfunction "5_5") (pintype "passive"))
      (node (ref "U24") (pin "P22") (pinfunction "IO_B5_P22_P22") (pintype "bidirectional"))
    )
    (net (code "237") (name "Net-(U24F-IO_B5_R21)") (class "Default")
      (node (ref "R44") (pin "8") (pinfunction "8_8") (pintype "passive"))
      (node (ref "U24") (pin "R21") (pinfunction "IO_B5_R21_R21") (pintype "bidirectional"))
    )
    (net (code "238") (name "Net-(U24F-IO_B5_R22)") (class "Default")
      (node (ref "R44") (pin "7") (pinfunction "7_7") (pintype "passive"))
      (node (ref "U24") (pin "R22") (pinfunction "IO_B5_R22_R22") (pintype "bidirectional"))
    )
    (net (code "239") (name "Net-(U24F-IO_B5_U21)") (class "Default")
      (node (ref "R41") (pin "6") (pinfunction "6_6") (pintype "passive"))
      (node (ref "U24") (pin "U21") (pinfunction "IO_B5_U21_U21") (pintype "bidirectional"))
    )
    (net (code "240") (name "Net-(U24F-IO_B5_U22)") (class "Default")
      (node (ref "R41") (pin "5") (pinfunction "5_5") (pintype "passive"))
      (node (ref "U24") (pin "U22") (pinfunction "IO_B5_U22_U22") (pintype "bidirectional"))
    )
    (net (code "241") (name "Net-(U24F-IO_B5_V21)") (class "Default")
      (node (ref "R41") (pin "8") (pinfunction "8_8") (pintype "passive"))
      (node (ref "U24") (pin "V21") (pinfunction "IO_B5_V21_V21") (pintype "bidirectional"))
    )
    (net (code "242") (name "Net-(U24F-IO_B5_V22)") (class "Default")
      (node (ref "R41") (pin "7") (pinfunction "7_7") (pintype "passive"))
      (node (ref "U24") (pin "V22") (pinfunction "IO_B5_V22_V22") (pintype "bidirectional"))
    )
    (net (code "243") (name "Net-(U24F-IO_B5_W21)") (class "Default")
      (node (ref "R40") (pin "6") (pinfunction "6_6") (pintype "passive"))
      (node (ref "U24") (pin "W21") (pinfunction "IO_B5_W21_W21") (pintype "bidirectional"))
    )
    (net (code "244") (name "Net-(U24F-IO_B5_W22)") (class "Default")
      (node (ref "R40") (pin "5") (pinfunction "5_5") (pintype "passive"))
      (node (ref "U24") (pin "W22") (pinfunction "IO_B5_W22_W22") (pintype "bidirectional"))
    )
    (net (code "245") (name "Net-(U24F-IO_B5_Y21)") (class "Default")
      (node (ref "R40") (pin "8") (pinfunction "8_8") (pintype "passive"))
      (node (ref "U24") (pin "Y21") (pinfunction "IO_B5_Y21_Y21") (pintype "bidirectional"))
    )
    (net (code "246") (name "Net-(U24F-IO_B5_Y22)") (class "Default")
      (node (ref "R40") (pin "7") (pinfunction "7_7") (pintype "passive"))
      (node (ref "U24") (pin "Y22") (pinfunction "IO_B5_Y22_Y22") (pintype "bidirectional"))
    )
    (net (code "247") (name "unconnected-(U24B-IO_B1_J7-PadJ7)") (class "Default")
      (node (ref "U24") (pin "J7") (pinfunction "IO_B1_J7_J7") (pintype "bidirectional"))
    )
    (net (code "248") (name "unconnected-(U24B-IO_B1_K7-PadK7)") (class "Default")
      (node (ref "U24") (pin "K7") (pinfunction "IO_B1_K7_K7") (pintype "bidirectional"))
    )
    (net (code "249") (name "unconnected-(U24B-IO_B1_K8-PadK8)") (class "Default")
      (node (ref "U24") (pin "K8") (pinfunction "IO_B1_K8_K8") (pintype "bidirectional"))
    )
    (net (code "250") (name "unconnected-(U24B-IO_B1_L8-PadL8)") (class "Default")
      (node (ref "U24") (pin "L8") (pinfunction "IO_B1_L8_L8") (pintype "bidirectional"))
    )
    (net (code "251") (name "unconnected-(U24C-IO_B2_L7-PadL7)") (class "Default")
      (node (ref "U24") (pin "L7") (pinfunction "IO_B2_L7_L7") (pintype "bidirectional"))
    )
    (net (code "252") (name "unconnected-(U24C-IO_B2_T4-PadT4)") (class "Default")
      (node (ref "U24") (pin "T4") (pinfunction "IO_B2_T4_T4") (pintype "bidirectional"))
    )
    (net (code "253") (name "unconnected-(U24C-IO_B2_V3{slash}RDN1-PadV3)") (class "Default")
      (node (ref "U24") (pin "V3") (pinfunction "IO_B2_V3/RDN1_V3") (pintype "bidirectional"))
    )
    (net (code "254") (name "unconnected-(U24C-IO_B2_V4{slash}RUP1-PadV4)") (class "Default")
      (node (ref "U24") (pin "V4") (pinfunction "IO_B2_V4/RUP1_V4") (pintype "bidirectional"))
    )
    (net (code "255") (name "unconnected-(U24C-IO_B2_W2-PadW2)") (class "Default")
      (node (ref "U24") (pin "W2") (pinfunction "IO_B2_W2_W2") (pintype "bidirectional"))
    )
    (net (code "256") (name "unconnected-(U24C-IO_B2_Y2-PadY2)") (class "Default")
      (node (ref "U24") (pin "Y2") (pinfunction "IO_B2_Y2_Y2") (pintype "bidirectional"))
    )
    (net (code "257") (name "unconnected-(U24D-IO_B3_AA3{slash}PLL1_CLKOUTP-PadAA3)") (class "Default")
      (node (ref "U24") (pin "AA3") (pinfunction "IO_B3_AA3/PLL1_CLKOUTP_AA3") (pintype "bidirectional"))
    )
    (net (code "258") (name "unconnected-(U24D-IO_B3_AB3{slash}PLL1_CLKOUTN-PadAB3)") (class "Default")
      (node (ref "U24") (pin "AB3") (pinfunction "IO_B3_AB3/PLL1_CLKOUTN_AB3") (pintype "bidirectional"))
    )
    (net (code "259") (name "unconnected-(U24D-IO_B3_AB10-PadAB10)") (class "Default")
      (node (ref "U24") (pin "AB10") (pinfunction "IO_B3_AB10_AB10") (pintype "bidirectional"))
    )
    (net (code "260") (name "unconnected-(U24D-IO_B3_R11-PadR11)") (class "Default")
      (node (ref "U24") (pin "R11") (pinfunction "IO_B3_R11_R11") (pintype "bidirectional"))
    )
    (net (code "261") (name "unconnected-(U24D-IO_B3_R12-PadR12)") (class "Default")
      (node (ref "U24") (pin "R12") (pinfunction "IO_B3_R12_R12") (pintype "bidirectional"))
    )
    (net (code "262") (name "unconnected-(U24D-IO_B3_T11-PadT11)") (class "Default")
      (node (ref "U24") (pin "T11") (pinfunction "IO_B3_T11_T11") (pintype "bidirectional"))
    )
    (net (code "263") (name "unconnected-(U24D-IO_B3_U11-PadU11)") (class "Default")
      (node (ref "U24") (pin "U11") (pinfunction "IO_B3_U11_U11") (pintype "bidirectional"))
    )
    (net (code "264") (name "unconnected-(U24D-IO_B3_V10-PadV10)") (class "Default")
      (node (ref "U24") (pin "V10") (pinfunction "IO_B3_V10_V10") (pintype "bidirectional"))
    )
    (net (code "265") (name "unconnected-(U24D-IO_B3_W8-PadW8)") (class "Default")
      (node (ref "U24") (pin "W8") (pinfunction "IO_B3_W8_W8") (pintype "bidirectional"))
    )
    (net (code "266") (name "unconnected-(U24D-IO_B3_Y3-PadY3)") (class "Default")
      (node (ref "U24") (pin "Y3") (pinfunction "IO_B3_Y3_Y3") (pintype "bidirectional"))
    )
    (net (code "267") (name "unconnected-(U24E-IO_B4_AA18-PadAA18)") (class "Default")
      (node (ref "U24") (pin "AA18") (pinfunction "IO_B4_AA18_AA18") (pintype "bidirectional"))
    )
    (net (code "268") (name "unconnected-(U24E-IO_B4_AA19{slash}RUP2-PadAA19)") (class "Default")
      (node (ref "U24") (pin "AA19") (pinfunction "IO_B4_AA19/RUP2_AA19") (pintype "bidirectional"))
    )
    (net (code "269") (name "unconnected-(U24E-IO_B4_AB19{slash}RDN2-PadAB19)") (class "Default")
      (node (ref "U24") (pin "AB19") (pinfunction "IO_B4_AB19/RDN2_AB19") (pintype "bidirectional"))
    )
    (net (code "270") (name "unconnected-(U24E-IO_B4_R13-PadR13)") (class "Default")
      (node (ref "U24") (pin "R13") (pinfunction "IO_B4_R13_R13") (pintype "bidirectional"))
    )
    (net (code "271") (name "unconnected-(U24E-IO_B4_R16{slash}PLL4_CLKOUTN-PadR16)") (class "Default")
      (node (ref "U24") (pin "R16") (pinfunction "IO_B4_R16/PLL4_CLKOUTN_R16") (pintype "bidirectional"))
    )
    (net (code "272") (name "unconnected-(U24E-IO_B4_T16{slash}PLL4_CLKOUTP-PadT16)") (class "Default")
      (node (ref "U24") (pin "T16") (pinfunction "IO_B4_T16/PLL4_CLKOUTP_T16") (pintype "bidirectional"))
    )
    (net (code "273") (name "unconnected-(U24E-IO_B4_V12-PadV12)") (class "Default")
      (node (ref "U24") (pin "V12") (pinfunction "IO_B4_V12_V12") (pintype "bidirectional"))
    )
    (net (code "274") (name "unconnected-(U24E-IO_B4_V13-PadV13)") (class "Default")
      (node (ref "U24") (pin "V13") (pinfunction "IO_B4_V13_V13") (pintype "bidirectional"))
    )
    (net (code "275") (name "unconnected-(U24F-IO_B5_AA21-PadAA21)") (class "Default")
      (node (ref "U24") (pin "AA21") (pinfunction "IO_B5_AA21_AA21") (pintype "bidirectional"))
    )
    (net (code "276") (name "unconnected-(U24F-IO_B5_AA22-PadAA22)") (class "Default")
      (node (ref "U24") (pin "AA22") (pinfunction "IO_B5_AA22_AA22") (pintype "bidirectional"))
    )
    (net (code "277") (name "unconnected-(U24F-IO_B5_M15-PadM15)") (class "Default")
      (node (ref "U24") (pin "M15") (pinfunction "IO_B5_M15_M15") (pintype "bidirectional"))
    )
    (net (code "278") (name "unconnected-(U24F-IO_B5_M16-PadM16)") (class "Default")
      (node (ref "U24") (pin "M16") (pinfunction "IO_B5_M16_M16") (pintype "bidirectional"))
    )
    (net (code "279") (name "unconnected-(U24F-IO_B5_M19-PadM19)") (class "Default")
      (node (ref "U24") (pin "M19") (pinfunction "IO_B5_M19_M19") (pintype "bidirectional"))
    )
    (net (code "280") (name "unconnected-(U24F-IO_B5_M20-PadM20)") (class "Default")
      (node (ref "U24") (pin "M20") (pinfunction "IO_B5_M20_M20") (pintype "bidirectional"))
    )
    (net (code "281") (name "unconnected-(U24F-IO_B5_N14-PadN14)") (class "Default")
      (node (ref "U24") (pin "N14") (pinfunction "IO_B5_N14_N14") (pintype "bidirectional"))
    )
    (net (code "282") (name "unconnected-(U24F-IO_B5_N15-PadN15)") (class "Default")
      (node (ref "U24") (pin "N15") (pinfunction "IO_B5_N15_N15") (pintype "bidirectional"))
    )
    (net (code "283") (name "unconnected-(U24F-IO_B5_N16-PadN16)") (class "Default")
      (node (ref "U24") (pin "N16") (pinfunction "IO_B5_N16_N16") (pintype "bidirectional"))
    )
    (net (code "284") (name "unconnected-(U24F-IO_B5_N17-PadN17)") (class "Default")
      (node (ref "U24") (pin "N17") (pinfunction "IO_B5_N17_N17") (pintype "bidirectional"))
    )
    (net (code "285") (name "unconnected-(U24F-IO_B5_N18-PadN18)") (class "Default")
      (node (ref "U24") (pin "N18") (pinfunction "IO_B5_N18_N18") (pintype "bidirectional"))
    )
    (net (code "286") (name "unconnected-(U24F-IO_B5_P14-PadP14)") (class "Default")
      (node (ref "U24") (pin "P14") (pinfunction "IO_B5_P14_P14") (pintype "bidirectional"))
    )
    (net (code "287") (name "unconnected-(U24F-IO_B5_P15-PadP15)") (class "Default")
      (node (ref "U24") (pin "P15") (pinfunction "IO_B5_P15_P15") (pintype "bidirectional"))
    )
    (net (code "288") (name "unconnected-(U24F-IO_B5_P16-PadP16)") (class "Default")
      (node (ref "U24") (pin "P16") (pinfunction "IO_B5_P16_P16") (pintype "bidirectional"))
    )
    (net (code "289") (name "unconnected-(U24F-IO_B5_P17-PadP17)") (class "Default")
      (node (ref "U24") (pin "P17") (pinfunction "IO_B5_P17_P17") (pintype "bidirectional"))
    )
    (net (code "290") (name "unconnected-(U24F-IO_B5_R18-PadR18)") (class "Default")
      (node (ref "U24") (pin "R18") (pinfunction "IO_B5_R18_R18") (pintype "bidirectional"))
    )
    (net (code "291") (name "unconnected-(U24F-IO_B5_R19-PadR19)") (class "Default")
      (node (ref "U24") (pin "R19") (pinfunction "IO_B5_R19_R19") (pintype "bidirectional"))
    )
    (net (code "292") (name "unconnected-(U24F-IO_B5_R20-PadR20)") (class "Default")
      (node (ref "U24") (pin "R20") (pinfunction "IO_B5_R20_R20") (pintype "bidirectional"))
    )
    (net (code "293") (name "unconnected-(U24F-IO_B5_T17{slash}RUP3-PadT17)") (class "Default")
      (node (ref "U24") (pin "T17") (pinfunction "IO_B5_T17/RUP3_T17") (pintype "bidirectional"))
    )
    (net (code "294") (name "unconnected-(U24F-IO_B5_T18{slash}RDN3-PadT18)") (class "Default")
      (node (ref "U24") (pin "T18") (pinfunction "IO_B5_T18/RDN3_T18") (pintype "bidirectional"))
    )
    (net (code "295") (name "unconnected-(U24F-IO_B5_U19-PadU19)") (class "Default")
      (node (ref "U24") (pin "U19") (pinfunction "IO_B5_U19_U19") (pintype "bidirectional"))
    )
    (net (code "296") (name "unconnected-(U24F-IO_B5_U20-PadU20)") (class "Default")
      (node (ref "U24") (pin "U20") (pinfunction "IO_B5_U20_U20") (pintype "bidirectional"))
    )
    (net (code "297") (name "unconnected-(U24F-IO_B5_W19-PadW19)") (class "Default")
      (node (ref "U24") (pin "W19") (pinfunction "IO_B5_W19_W19") (pintype "bidirectional"))
    )
    (net (code "298") (name "unconnected-(U24F-IO_B5_W20-PadW20)") (class "Default")
      (node (ref "U24") (pin "W20") (pinfunction "IO_B5_W20_W20") (pintype "bidirectional"))
    )
    (net (code "299") (name "unconnected-(U24G-IO_B6_C20-PadC20)") (class "Default")
      (node (ref "U24") (pin "C20") (pinfunction "IO_B6_C20_C20") (pintype "bidirectional"))
    )
    (net (code "300") (name "unconnected-(U24G-IO_B6_D20-PadD20)") (class "Default")
      (node (ref "U24") (pin "D20") (pinfunction "IO_B6_D20_D20") (pintype "bidirectional"))
    )
    (net (code "301") (name "unconnected-(U24G-IO_B6_J15-PadJ15)") (class "Default")
      (node (ref "U24") (pin "J15") (pinfunction "IO_B6_J15_J15") (pintype "bidirectional"))
    )
    (net (code "302") (name "unconnected-(U24G-IO_B6_J16-PadJ16)") (class "Default")
      (node (ref "U24") (pin "J16") (pinfunction "IO_B6_J16_J16") (pintype "bidirectional"))
    )
    (net (code "303") (name "unconnected-(U24G-IO_B6_J18-PadJ18)") (class "Default")
      (node (ref "U24") (pin "J18") (pinfunction "IO_B6_J18_J18") (pintype "bidirectional"))
    )
    (net (code "304") (name "unconnected-(U24G-IO_B6_K15-PadK15)") (class "Default")
      (node (ref "U24") (pin "K15") (pinfunction "IO_B6_K15_K15") (pintype "bidirectional"))
    )
    (net (code "305") (name "unconnected-(U24G-IO_B6_K16-PadK16)") (class "Default")
      (node (ref "U24") (pin "K16") (pinfunction "IO_B6_K16_K16") (pintype "bidirectional"))
    )
    (net (code "306") (name "unconnected-(U24H-IO_B7_A13-PadA13)") (class "Default")
      (node (ref "U24") (pin "A13") (pinfunction "IO_B7_A13_A13") (pintype "bidirectional"))
    )
    (net (code "307") (name "unconnected-(U24H-IO_B7_A18-PadA18)") (class "Default")
      (node (ref "U24") (pin "A18") (pinfunction "IO_B7_A18_A18") (pintype "bidirectional"))
    )
    (net (code "308") (name "unconnected-(U24H-IO_B7_A19{slash}RDN4-PadA19)") (class "Default")
      (node (ref "U24") (pin "A19") (pinfunction "IO_B7_A19/RDN4_A19") (pintype "bidirectional"))
    )
    (net (code "309") (name "unconnected-(U24H-IO_B7_A20{slash}PLL2_CLKOUTN-PadA20)") (class "Default")
      (node (ref "U24") (pin "A20") (pinfunction "IO_B7_A20/PLL2_CLKOUTN_A20") (pintype "bidirectional"))
    )
    (net (code "310") (name "unconnected-(U24H-IO_B7_B13-PadB13)") (class "Default")
      (node (ref "U24") (pin "B13") (pinfunction "IO_B7_B13_B13") (pintype "bidirectional"))
    )
    (net (code "311") (name "unconnected-(U24H-IO_B7_B18-PadB18)") (class "Default")
      (node (ref "U24") (pin "B18") (pinfunction "IO_B7_B18_B18") (pintype "bidirectional"))
    )
    (net (code "312") (name "unconnected-(U24H-IO_B7_B19{slash}RUP4-PadB19)") (class "Default")
      (node (ref "U24") (pin "B19") (pinfunction "IO_B7_B19/RUP4_B19") (pintype "bidirectional"))
    )
    (net (code "313") (name "unconnected-(U24H-IO_B7_B20{slash}PLL2_CLKOUTP-PadB20)") (class "Default")
      (node (ref "U24") (pin "B20") (pinfunction "IO_B7_B20/PLL2_CLKOUTP_B20") (pintype "bidirectional"))
    )
    (net (code "314") (name "unconnected-(U24H-IO_B7_C13-PadC13)") (class "Default")
      (node (ref "U24") (pin "C13") (pinfunction "IO_B7_C13_C13") (pintype "bidirectional"))
    )
    (net (code "315") (name "unconnected-(U24H-IO_B7_C17-PadC17)") (class "Default")
      (node (ref "U24") (pin "C17") (pinfunction "IO_B7_C17_C17") (pintype "bidirectional"))
    )
    (net (code "316") (name "unconnected-(U24H-IO_B7_C19-PadC19)") (class "Default")
      (node (ref "U24") (pin "C19") (pinfunction "IO_B7_C19_C19") (pintype "bidirectional"))
    )
    (net (code "317") (name "unconnected-(U24H-IO_B7_D13-PadD13)") (class "Default")
      (node (ref "U24") (pin "D13") (pinfunction "IO_B7_D13_D13") (pintype "bidirectional"))
    )
    (net (code "318") (name "unconnected-(U24H-IO_B7_D15-PadD15)") (class "Default")
      (node (ref "U24") (pin "D15") (pinfunction "IO_B7_D15_D15") (pintype "bidirectional"))
    )
    (net (code "319") (name "unconnected-(U24H-IO_B7_D19-PadD19)") (class "Default")
      (node (ref "U24") (pin "D19") (pinfunction "IO_B7_D19_D19") (pintype "bidirectional"))
    )
    (net (code "320") (name "unconnected-(U24H-IO_B7_E11-PadE11)") (class "Default")
      (node (ref "U24") (pin "E11") (pinfunction "IO_B7_E11_E11") (pintype "bidirectional"))
    )
    (net (code "321") (name "unconnected-(U24H-IO_B7_E12-PadE12)") (class "Default")
      (node (ref "U24") (pin "E12") (pinfunction "IO_B7_E12_E12") (pintype "bidirectional"))
    )
    (net (code "322") (name "unconnected-(U24H-IO_B7_E13-PadE13)") (class "Default")
      (node (ref "U24") (pin "E13") (pinfunction "IO_B7_E13_E13") (pintype "bidirectional"))
    )
    (net (code "323") (name "unconnected-(U24H-IO_B7_E14-PadE14)") (class "Default")
      (node (ref "U24") (pin "E14") (pinfunction "IO_B7_E14_E14") (pintype "bidirectional"))
    )
    (net (code "324") (name "unconnected-(U24H-IO_B7_E15-PadE15)") (class "Default")
      (node (ref "U24") (pin "E15") (pinfunction "IO_B7_E15_E15") (pintype "bidirectional"))
    )
    (net (code "325") (name "unconnected-(U24H-IO_B7_E16-PadE16)") (class "Default")
      (node (ref "U24") (pin "E16") (pinfunction "IO_B7_E16_E16") (pintype "bidirectional"))
    )
    (net (code "326") (name "unconnected-(U24H-IO_B7_F11-PadF11)") (class "Default")
      (node (ref "U24") (pin "F11") (pinfunction "IO_B7_F11_F11") (pintype "bidirectional"))
    )
    (net (code "327") (name "unconnected-(U24H-IO_B7_F12-PadF12)") (class "Default")
      (node (ref "U24") (pin "F12") (pinfunction "IO_B7_F12_F12") (pintype "bidirectional"))
    )
    (net (code "328") (name "unconnected-(U24H-IO_B7_F13-PadF13)") (class "Default")
      (node (ref "U24") (pin "F13") (pinfunction "IO_B7_F13_F13") (pintype "bidirectional"))
    )
    (net (code "329") (name "unconnected-(U24H-IO_B7_F14-PadF14)") (class "Default")
      (node (ref "U24") (pin "F14") (pinfunction "IO_B7_F14_F14") (pintype "bidirectional"))
    )
    (net (code "330") (name "unconnected-(U24H-IO_B7_F15-PadF15)") (class "Default")
      (node (ref "U24") (pin "F15") (pinfunction "IO_B7_F15_F15") (pintype "bidirectional"))
    )
    (net (code "331") (name "unconnected-(U24H-IO_B7_F16-PadF16)") (class "Default")
      (node (ref "U24") (pin "F16") (pinfunction "IO_B7_F16_F16") (pintype "bidirectional"))
    )
    (net (code "332") (name "unconnected-(U24H-IO_B7_G12-PadG12)") (class "Default")
      (node (ref "U24") (pin "G12") (pinfunction "IO_B7_G12_G12") (pintype "bidirectional"))
    )
    (net (code "333") (name "unconnected-(U24H-IO_B7_G13-PadG13)") (class "Default")
      (node (ref "U24") (pin "G13") (pinfunction "IO_B7_G13_G13") (pintype "bidirectional"))
    )
    (net (code "334") (name "unconnected-(U24H-IO_B7_G14-PadG14)") (class "Default")
      (node (ref "U24") (pin "G14") (pinfunction "IO_B7_G14_G14") (pintype "bidirectional"))
    )
    (net (code "335") (name "unconnected-(U24H-IO_B7_G15-PadG15)") (class "Default")
      (node (ref "U24") (pin "G15") (pinfunction "IO_B7_G15_G15") (pintype "bidirectional"))
    )
    (net (code "336") (name "unconnected-(U24H-IO_B7_G16-PadG16)") (class "Default")
      (node (ref "U24") (pin "G16") (pinfunction "IO_B7_G16_G16") (pintype "bidirectional"))
    )
    (net (code "337") (name "unconnected-(U24H-IO_B7_H12-PadH12)") (class "Default")
      (node (ref "U24") (pin "H12") (pinfunction "IO_B7_H12_H12") (pintype "bidirectional"))
    )
    (net (code "338") (name "unconnected-(U24H-IO_B7_H13-PadH13)") (class "Default")
      (node (ref "U24") (pin "H13") (pinfunction "IO_B7_H13_H13") (pintype "bidirectional"))
    )
    (net (code "339") (name "unconnected-(U24H-IO_B7_H14-PadH14)") (class "Default")
      (node (ref "U24") (pin "H14") (pinfunction "IO_B7_H14_H14") (pintype "bidirectional"))
    )
    (net (code "340") (name "unconnected-(U24H-IO_B7_H15-PadH15)") (class "Default")
      (node (ref "U24") (pin "H15") (pinfunction "IO_B7_H15_H15") (pintype "bidirectional"))
    )
    (net (code "341") (name "unconnected-(U24I-IO_B8_A3-PadA3)") (class "Default")
      (node (ref "U24") (pin "A3") (pinfunction "IO_B8_A3_A3") (pintype "bidirectional"))
    )
    (net (code "342") (name "unconnected-(U24I-IO_B8_A4-PadA4)") (class "Default")
      (node (ref "U24") (pin "A4") (pinfunction "IO_B8_A4_A4") (pintype "bidirectional"))
    )
    (net (code "343") (name "unconnected-(U24I-IO_B8_A6-PadA6)") (class "Default")
      (node (ref "U24") (pin "A6") (pinfunction "IO_B8_A6_A6") (pintype "bidirectional"))
    )
    (net (code "344") (name "unconnected-(U24I-IO_B8_A7-PadA7)") (class "Default")
      (node (ref "U24") (pin "A7") (pinfunction "IO_B8_A7_A7") (pintype "bidirectional"))
    )
    (net (code "345") (name "unconnected-(U24I-IO_B8_A9-PadA9)") (class "Default")
      (node (ref "U24") (pin "A9") (pinfunction "IO_B8_A9_A9") (pintype "bidirectional"))
    )
    (net (code "346") (name "unconnected-(U24I-IO_B8_A10-PadA10)") (class "Default")
      (node (ref "U24") (pin "A10") (pinfunction "IO_B8_A10_A10") (pintype "bidirectional"))
    )
    (net (code "347") (name "unconnected-(U24I-IO_B8_B3-PadB3)") (class "Default")
      (node (ref "U24") (pin "B3") (pinfunction "IO_B8_B3_B3") (pintype "bidirectional"))
    )
    (net (code "348") (name "unconnected-(U24I-IO_B8_B4-PadB4)") (class "Default")
      (node (ref "U24") (pin "B4") (pinfunction "IO_B8_B4_B4") (pintype "bidirectional"))
    )
    (net (code "349") (name "unconnected-(U24I-IO_B8_B5-PadB5)") (class "Default")
      (node (ref "U24") (pin "B5") (pinfunction "IO_B8_B5_B5") (pintype "bidirectional"))
    )
    (net (code "350") (name "unconnected-(U24I-IO_B8_B6-PadB6)") (class "Default")
      (node (ref "U24") (pin "B6") (pinfunction "IO_B8_B6_B6") (pintype "bidirectional"))
    )
    (net (code "351") (name "unconnected-(U24I-IO_B8_B9-PadB9)") (class "Default")
      (node (ref "U24") (pin "B9") (pinfunction "IO_B8_B9_B9") (pintype "bidirectional"))
    )
    (net (code "352") (name "unconnected-(U24I-IO_B8_B10-PadB10)") (class "Default")
      (node (ref "U24") (pin "B10") (pinfunction "IO_B8_B10_B10") (pintype "bidirectional"))
    )
    (net (code "353") (name "unconnected-(U24I-IO_B8_C3-PadC3)") (class "Default")
      (node (ref "U24") (pin "C3") (pinfunction "IO_B8_C3_C3") (pintype "bidirectional"))
    )
    (net (code "354") (name "unconnected-(U24I-IO_B8_C4-PadC4)") (class "Default")
      (node (ref "U24") (pin "C4") (pinfunction "IO_B8_C4_C4") (pintype "bidirectional"))
    )
    (net (code "355") (name "unconnected-(U24I-IO_B8_C7-PadC7)") (class "Default")
      (node (ref "U24") (pin "C7") (pinfunction "IO_B8_C7_C7") (pintype "bidirectional"))
    )
    (net (code "356") (name "unconnected-(U24I-IO_B8_C8-PadC8)") (class "Default")
      (node (ref "U24") (pin "C8") (pinfunction "IO_B8_C8_C8") (pintype "bidirectional"))
    )
    (net (code "357") (name "unconnected-(U24I-IO_B8_C10-PadC10)") (class "Default")
      (node (ref "U24") (pin "C10") (pinfunction "IO_B8_C10_C10") (pintype "bidirectional"))
    )
    (net (code "358") (name "unconnected-(U24I-IO_B8_D10-PadD10)") (class "Default")
      (node (ref "U24") (pin "D10") (pinfunction "IO_B8_D10_D10") (pintype "bidirectional"))
    )
    (net (code "359") (name "unconnected-(U24I-IO_B8_E7-PadE7)") (class "Default")
      (node (ref "U24") (pin "E7") (pinfunction "IO_B8_E7_E7") (pintype "bidirectional"))
    )
    (net (code "360") (name "unconnected-(U24I-IO_B8_E10-PadE10)") (class "Default")
      (node (ref "U24") (pin "E10") (pinfunction "IO_B8_E10_E10") (pintype "bidirectional"))
    )
    (net (code "361") (name "unconnected-(U24I-IO_B8_F7-PadF7)") (class "Default")
      (node (ref "U24") (pin "F7") (pinfunction "IO_B8_F7_F7") (pintype "bidirectional"))
    )
    (net (code "362") (name "unconnected-(U24I-IO_B8_F8-PadF8)") (class "Default")
      (node (ref "U24") (pin "F8") (pinfunction "IO_B8_F8_F8") (pintype "bidirectional"))
    )
    (net (code "363") (name "unconnected-(U24I-IO_B8_F9-PadF9)") (class "Default")
      (node (ref "U24") (pin "F9") (pinfunction "IO_B8_F9_F9") (pintype "bidirectional"))
    )
    (net (code "364") (name "unconnected-(U24I-IO_B8_G7-PadG7)") (class "Default")
      (node (ref "U24") (pin "G7") (pinfunction "IO_B8_G7_G7") (pintype "bidirectional"))
    )
    (net (code "365") (name "unconnected-(U24I-IO_B8_G8-PadG8)") (class "Default")
      (node (ref "U24") (pin "G8") (pinfunction "IO_B8_G8_G8") (pintype "bidirectional"))
    )
    (net (code "366") (name "unconnected-(U24I-IO_B8_G9-PadG9)") (class "Default")
      (node (ref "U24") (pin "G9") (pinfunction "IO_B8_G9_G9") (pintype "bidirectional"))
    )
    (net (code "367") (name "unconnected-(U24I-IO_B8_G10-PadG10)") (class "Default")
      (node (ref "U24") (pin "G10") (pinfunction "IO_B8_G10_G10") (pintype "bidirectional"))
    )
    (net (code "368") (name "unconnected-(U24I-IO_B8_G11-PadG11)") (class "Default")
      (node (ref "U24") (pin "G11") (pinfunction "IO_B8_G11_G11") (pintype "bidirectional"))
    )
    (net (code "369") (name "unconnected-(U24I-IO_B8_H9-PadH9)") (class "Default")
      (node (ref "U24") (pin "H9") (pinfunction "IO_B8_H9_H9") (pintype "bidirectional"))
    )
    (net (code "370") (name "unconnected-(U24I-IO_B8_H10-PadH10)") (class "Default")
      (node (ref "U24") (pin "H10") (pinfunction "IO_B8_H10_H10") (pintype "bidirectional"))
    )
    (net (code "371") (name "unconnected-(U24I-IO_B8_H11-PadH11)") (class "Default")
      (node (ref "U24") (pin "H11") (pinfunction "IO_B8_H11_H11") (pintype "bidirectional"))
    )
    (net (code "372") (name "unconnected-(U24J-CLK0_B1_G2{slash}DIFFCLK_0P-PadG2)") (class "Default")
      (node (ref "U24") (pin "G2") (pinfunction "CLK0_B1_G2/DIFFCLK_0P_G2") (pintype "bidirectional"))
    )
    (net (code "373") (name "unconnected-(U24J-CLK1_B1_G1{slash}DIFFCLK_0N-PadG1)") (class "Default")
      (node (ref "U24") (pin "G1") (pinfunction "CLK1_B1_G1/DIFFCLK_0N_G1") (pintype "bidirectional"))
    )
    (net (code "374") (name "unconnected-(U24J-CLK2_B2_T2{slash}DIFFCLK_1P-PadT2)") (class "Default")
      (node (ref "U24") (pin "T2") (pinfunction "CLK2_B2_T2/DIFFCLK_1P_T2") (pintype "bidirectional"))
    )
    (net (code "375") (name "unconnected-(U24J-CLK3_B2_T1{slash}DIFFCLK_1N-PadT1)") (class "Default")
      (node (ref "U24") (pin "T1") (pinfunction "CLK3_B2_T1/DIFFCLK_1N_T1") (pintype "bidirectional"))
    )
    (net (code "376") (name "unconnected-(U24J-CLK6_B5_T21{slash}DIFFCLK_3P-PadT21)") (class "Default")
      (node (ref "U24") (pin "T21") (pinfunction "CLK6_B5_T21/DIFFCLK_3P_T21") (pintype "bidirectional"))
    )
    (net (code "377") (name "unconnected-(U24J-CLK7_B5_T22{slash}DIFFCLK_3N-PadT22)") (class "Default")
      (node (ref "U24") (pin "T22") (pinfunction "CLK7_B5_T22/DIFFCLK_3N_T22") (pintype "bidirectional"))
    )
    (net (code "378") (name "unconnected-(U24J-CLK12_B4_AB12{slash}DIFFCLK_7N-PadAB12)") (class "Default")
      (node (ref "U24") (pin "AB12") (pinfunction "CLK12_B4_AB12/DIFFCLK_7N_AB12") (pintype "bidirectional"))
    )
    (net (code "379") (name "unconnected-(U24J-CLK13_B4_AA12{slash}DIFFCLK_7P-PadAA12)") (class "Default")
      (node (ref "U24") (pin "AA12") (pinfunction "CLK13_B4_AA12/DIFFCLK_7P_AA12") (pintype "bidirectional"))
    )
    (net (code "380") (name "unconnected-(U24J-CLK14_B3_AB11{slash}DIFFCLK_6N-PadAB11)") (class "Default")
      (node (ref "U24") (pin "AB11") (pinfunction "CLK14_B3_AB11/DIFFCLK_6N_AB11") (pintype "bidirectional"))
    )
    (net (code "381") (name "unconnected-(U24J-IO_B1_H7{slash}VREFB1N0-PadH7)") (class "Default")
      (node (ref "U24") (pin "H7") (pinfunction "IO_B1_H7/VREFB1N0_H7") (pintype "bidirectional"))
    )
    (net (code "382") (name "unconnected-(U24J-IO_B1_J3{slash}VREFB1N1-PadJ3)") (class "Default")
      (node (ref "U24") (pin "J3") (pinfunction "IO_B1_J3/VREFB1N1_J3") (pintype "bidirectional"))
    )
    (net (code "383") (name "unconnected-(U24J-IO_B2_M5{slash}VREFB2N0-PadM5)") (class "Default")
      (node (ref "U24") (pin "M5") (pinfunction "IO_B2_M5/VREFB2N0_M5") (pintype "bidirectional"))
    )
    (net (code "384") (name "unconnected-(U24J-IO_B2_T3{slash}VREFB2N1-PadT3)") (class "Default")
      (node (ref "U24") (pin "T3") (pinfunction "IO_B2_T3/VREFB2N1_T3") (pintype "bidirectional"))
    )
    (net (code "385") (name "unconnected-(U24J-IO_B3_V9{slash}VREFB3N0-PadV9)") (class "Default")
      (node (ref "U24") (pin "V9") (pinfunction "IO_B3_V9/VREFB3N0_V9") (pintype "bidirectional"))
    )
    (net (code "386") (name "unconnected-(U24J-IO_B3_Y4{slash}VREFB3N1-PadY4)") (class "Default")
      (node (ref "U24") (pin "Y4") (pinfunction "IO_B3_Y4/VREFB3N1_Y4") (pintype "bidirectional"))
    )
    (net (code "387") (name "unconnected-(U24J-IO_B4_V16{slash}VREFB4N0-PadV16)") (class "Default")
      (node (ref "U24") (pin "V16") (pinfunction "IO_B4_V16/VREFB4N0_V16") (pintype "bidirectional"))
    )
    (net (code "388") (name "unconnected-(U24J-IO_B4_W14{slash}VREFB4N1-PadW14)") (class "Default")
      (node (ref "U24") (pin "W14") (pinfunction "IO_B4_W14/VREFB4N1_W14") (pintype "bidirectional"))
    )
    (net (code "389") (name "unconnected-(U24J-IO_B5_P20{slash}VREFB5N0-PadP20)") (class "Default")
      (node (ref "U24") (pin "P20") (pinfunction "IO_B5_P20/VREFB5N0_P20") (pintype "bidirectional"))
    )
    (net (code "390") (name "unconnected-(U24J-IO_B5_R17{slash}VREFB5N1-PadR17)") (class "Default")
      (node (ref "U24") (pin "R17") (pinfunction "IO_B5_R17/VREFB5N1_R17") (pintype "bidirectional"))
    )
    (net (code "391") (name "unconnected-(U24J-IO_B6_H18{slash}VREFB6N0-PadH18)") (class "Default")
      (node (ref "U24") (pin "H18") (pinfunction "IO_B6_H18/VREFB6N0_H18") (pintype "bidirectional"))
    )
    (net (code "392") (name "unconnected-(U24J-IO_B6_K19{slash}VREFB6N1-PadK19)") (class "Default")
      (node (ref "U24") (pin "K19") (pinfunction "IO_B6_K19/VREFB6N1_K19") (pintype "bidirectional"))
    )
    (net (code "393") (name "unconnected-(U24J-IO_B7_C15{slash}VREFB7N1-PadC15)") (class "Default")
      (node (ref "U24") (pin "C15") (pinfunction "IO_B7_C15/VREFB7N1_C15") (pintype "bidirectional"))
    )
    (net (code "394") (name "unconnected-(U24J-IO_B7_D17{slash}VREFB7N0-PadD17)") (class "Default")
      (node (ref "U24") (pin "D17") (pinfunction "IO_B7_D17/VREFB7N0_D17") (pintype "bidirectional"))
    )
    (net (code "395") (name "unconnected-(U24J-IO_B8_D6{slash}VREFB8N1-PadD6)") (class "Default")
      (node (ref "U24") (pin "D6") (pinfunction "IO_B8_D6/VREFB8N1_D6") (pintype "bidirectional"))
    )
    (net (code "396") (name "unconnected-(U24J-IO_B8_E9{slash}VREFB8N0-PadE9)") (class "Default")
      (node (ref "U24") (pin "E9") (pinfunction "IO_B8_E9/VREFB8N0_E9") (pintype "bidirectional"))
    )
    (net (code "397") (name "unconnected-(U24K-IO_B6_K22{slash}NCEO-PadK22)") (class "Default")
      (node (ref "U24") (pin "K22") (pinfunction "IO_B6_K22/NCEO_K22") (pintype "bidirectional+no_connect"))
    )
    (net (code "398") (name "unconnected-(U24K-IO_B8_A5{slash}DATA5-PadA5)") (class "Default")
      (node (ref "U24") (pin "A5") (pinfunction "IO_B8_A5/DATA5_A5") (pintype "bidirectional+no_connect"))
    )
    (net (code "399") (name "unconnected-(U24K-IO_B8_A8{slash}DATA2-PadA8)") (class "Default")
      (node (ref "U24") (pin "A8") (pinfunction "IO_B8_A8/DATA2_A8") (pintype "bidirectional+no_connect"))
    )
    (net (code "400") (name "unconnected-(U24K-IO_B8_B7{slash}DATA4-PadB7)") (class "Default")
      (node (ref "U24") (pin "B7") (pinfunction "IO_B8_B7/DATA4_B7") (pintype "bidirectional+no_connect"))
    )
    (net (code "401") (name "unconnected-(U24K-IO_B8_B8{slash}DATA3-PadB8)") (class "Default")
      (node (ref "U24") (pin "B8") (pinfunction "IO_B8_B8/DATA3_B8") (pintype "bidirectional+no_connect"))
    )
    (net (code "402") (name "unconnected-(U24K-IO_B8_C6{slash}DATA7-PadC6)") (class "Default")
      (node (ref "U24") (pin "C6") (pinfunction "IO_B8_C6/DATA7_C6") (pintype "bidirectional+no_connect"))
    )
    (net (code "403") (name "unconnected-(U24K-IO_B8_F10{slash}DATA6-PadF10)") (class "Default")
      (node (ref "U24") (pin "F10") (pinfunction "IO_B8_F10/DATA6_F10") (pintype "bidirectional+no_connect"))
    )
  )
)
